# schematic1.net
KiCad netlist of a schematic drawn in Altium Designer
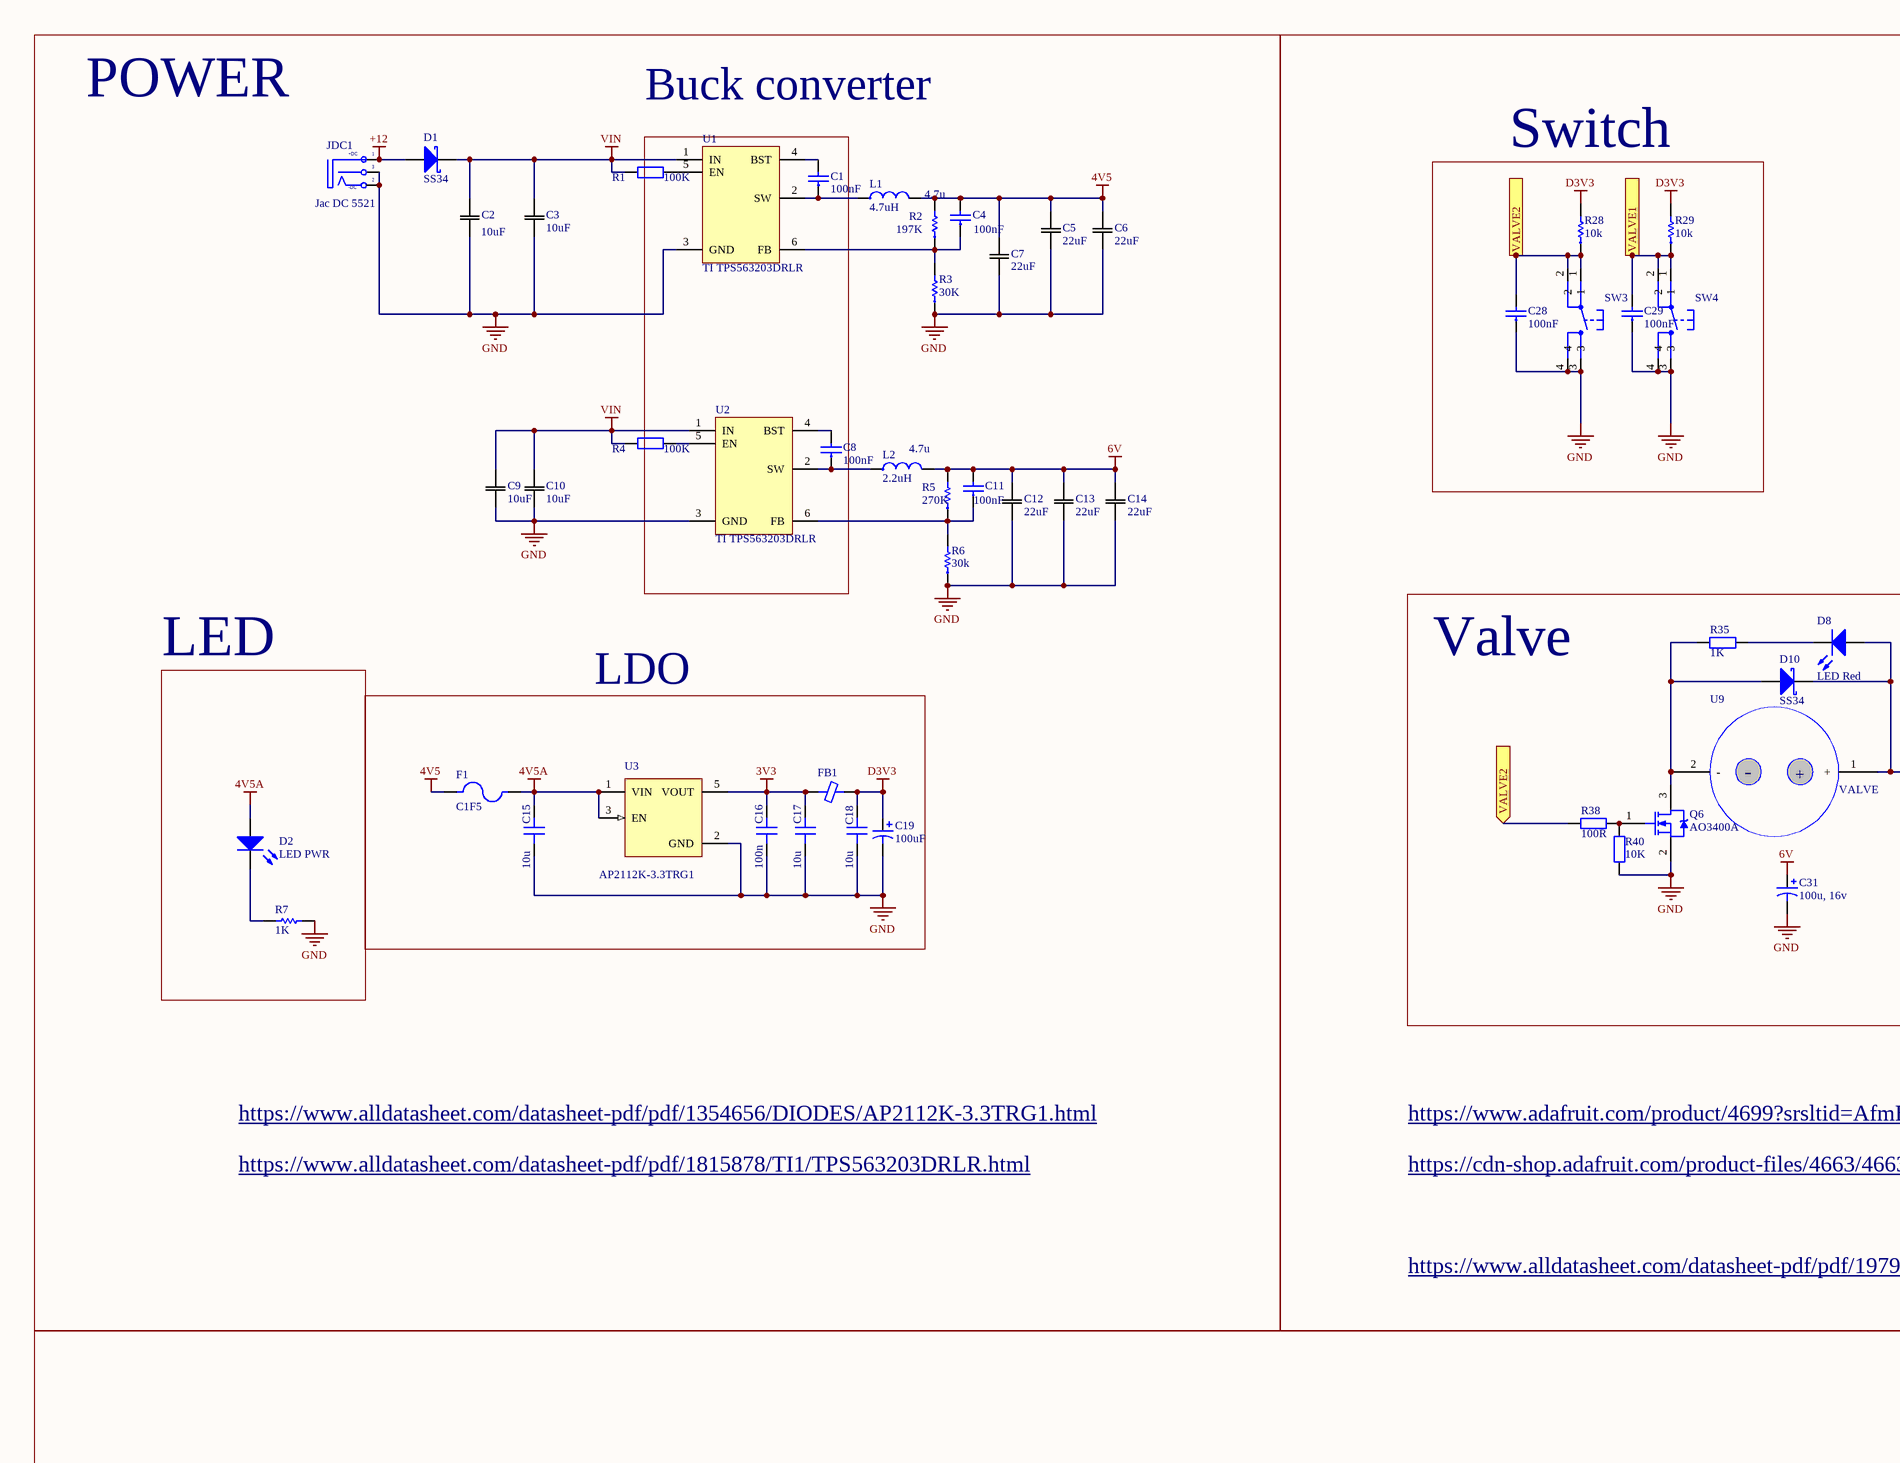
[diagram p0: schematic1.SchDoc, top left]
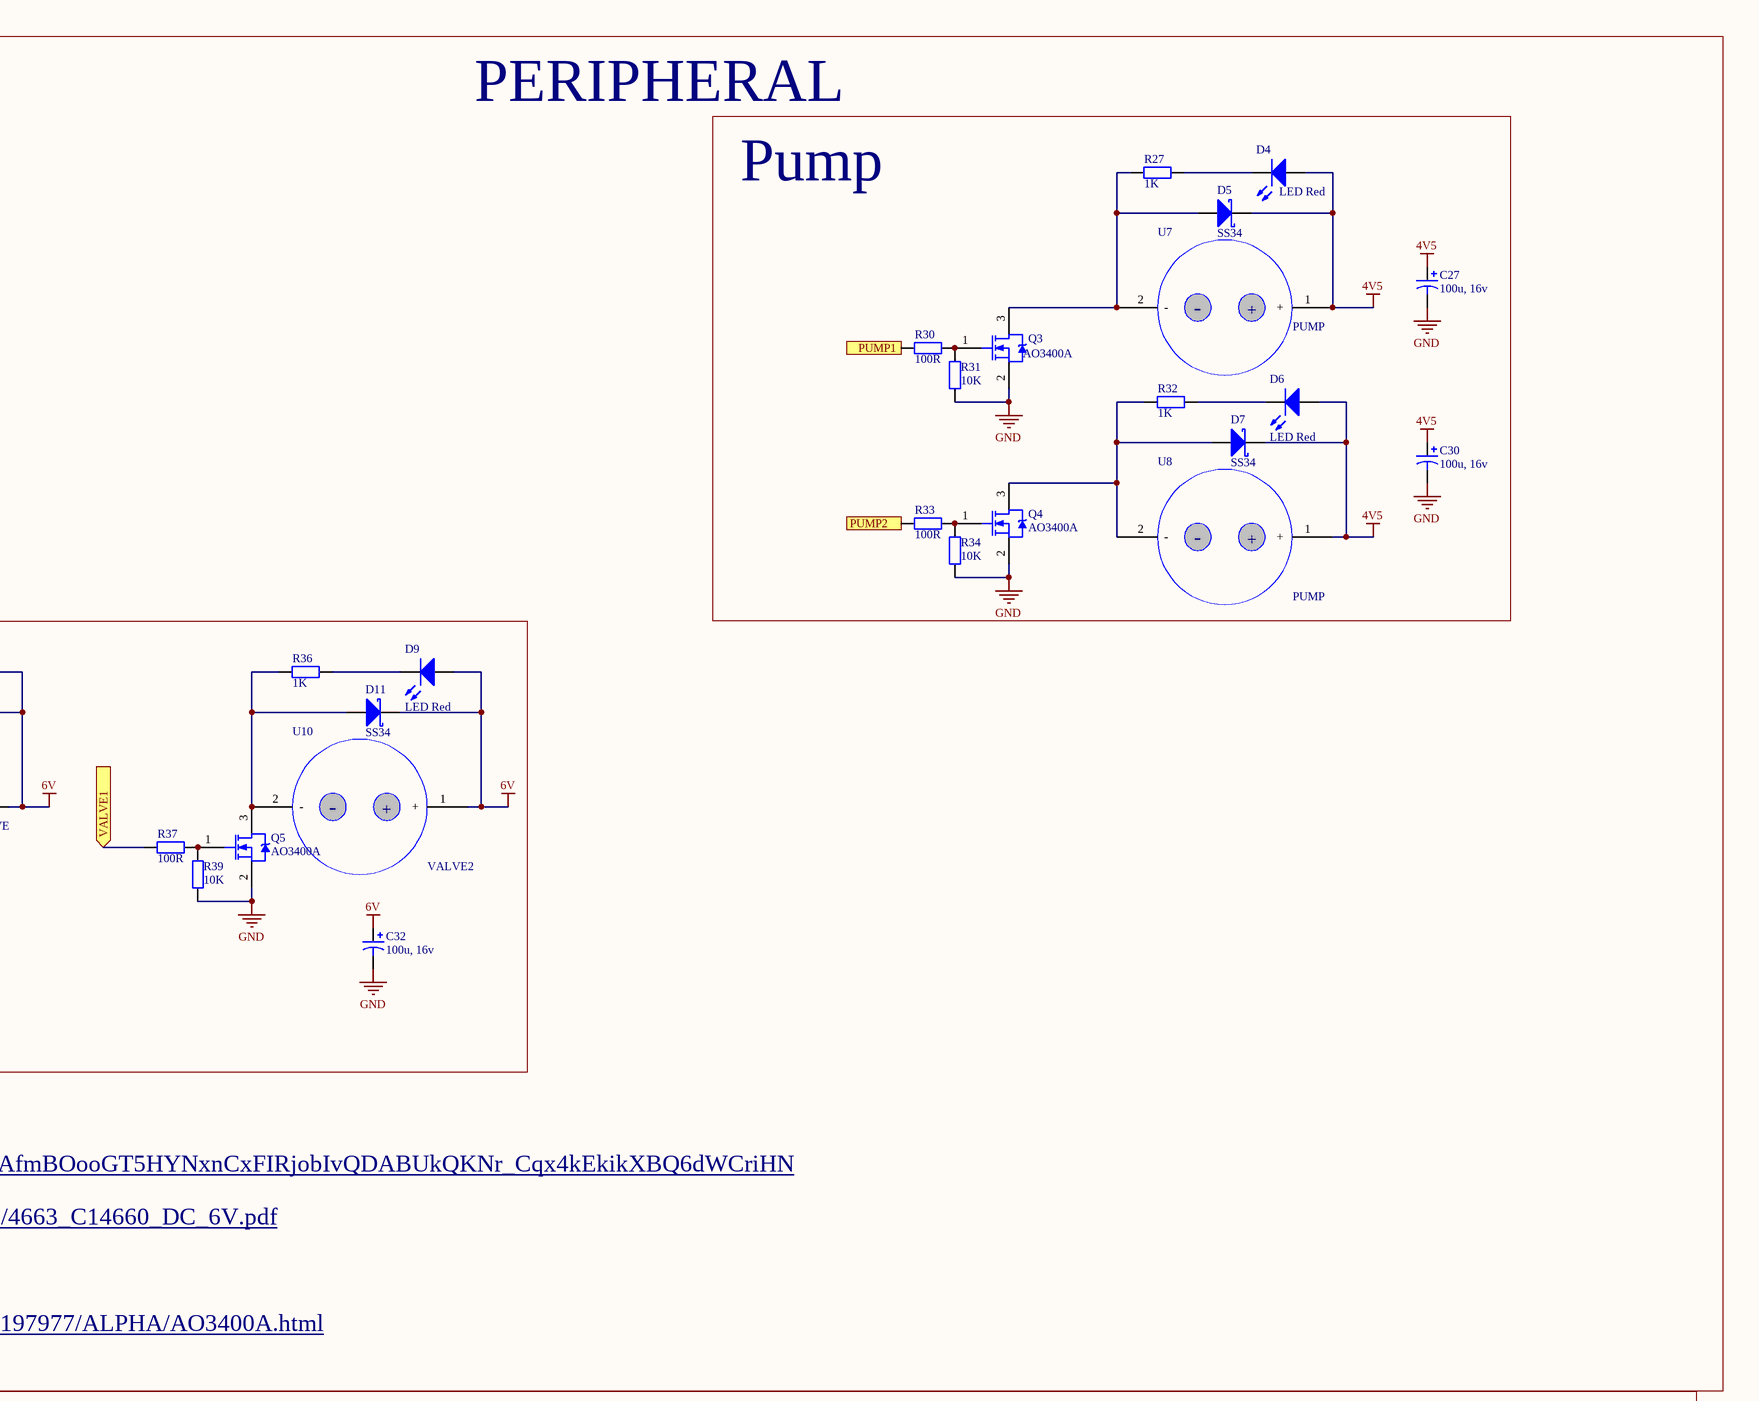
[diagram p1: schematic1.SchDoc, top right]
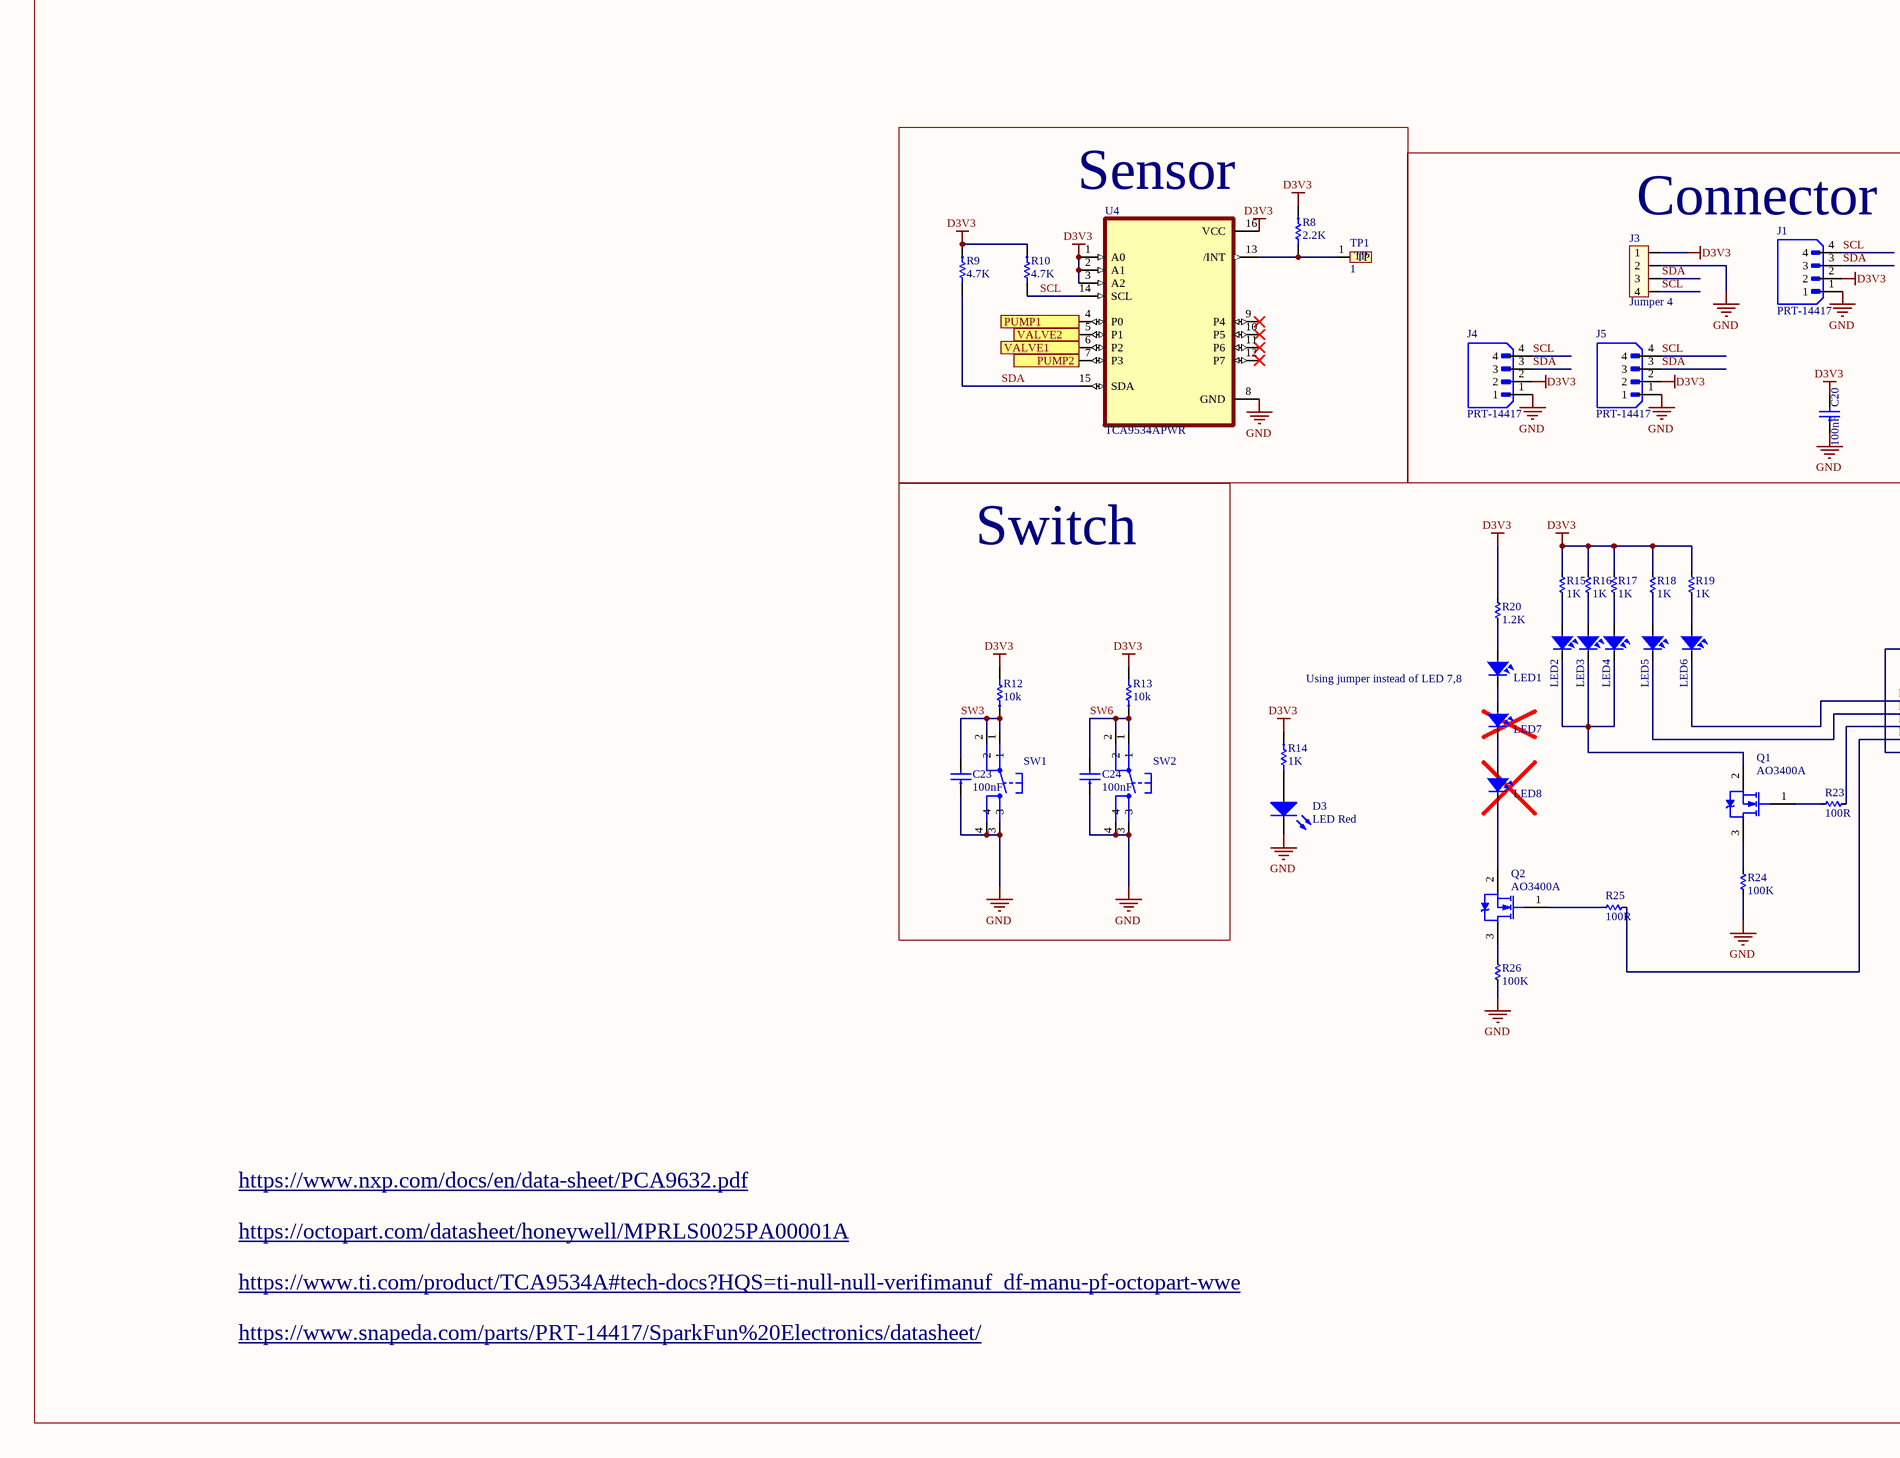
[diagram p2: schematic1.SchDoc, bottom left]
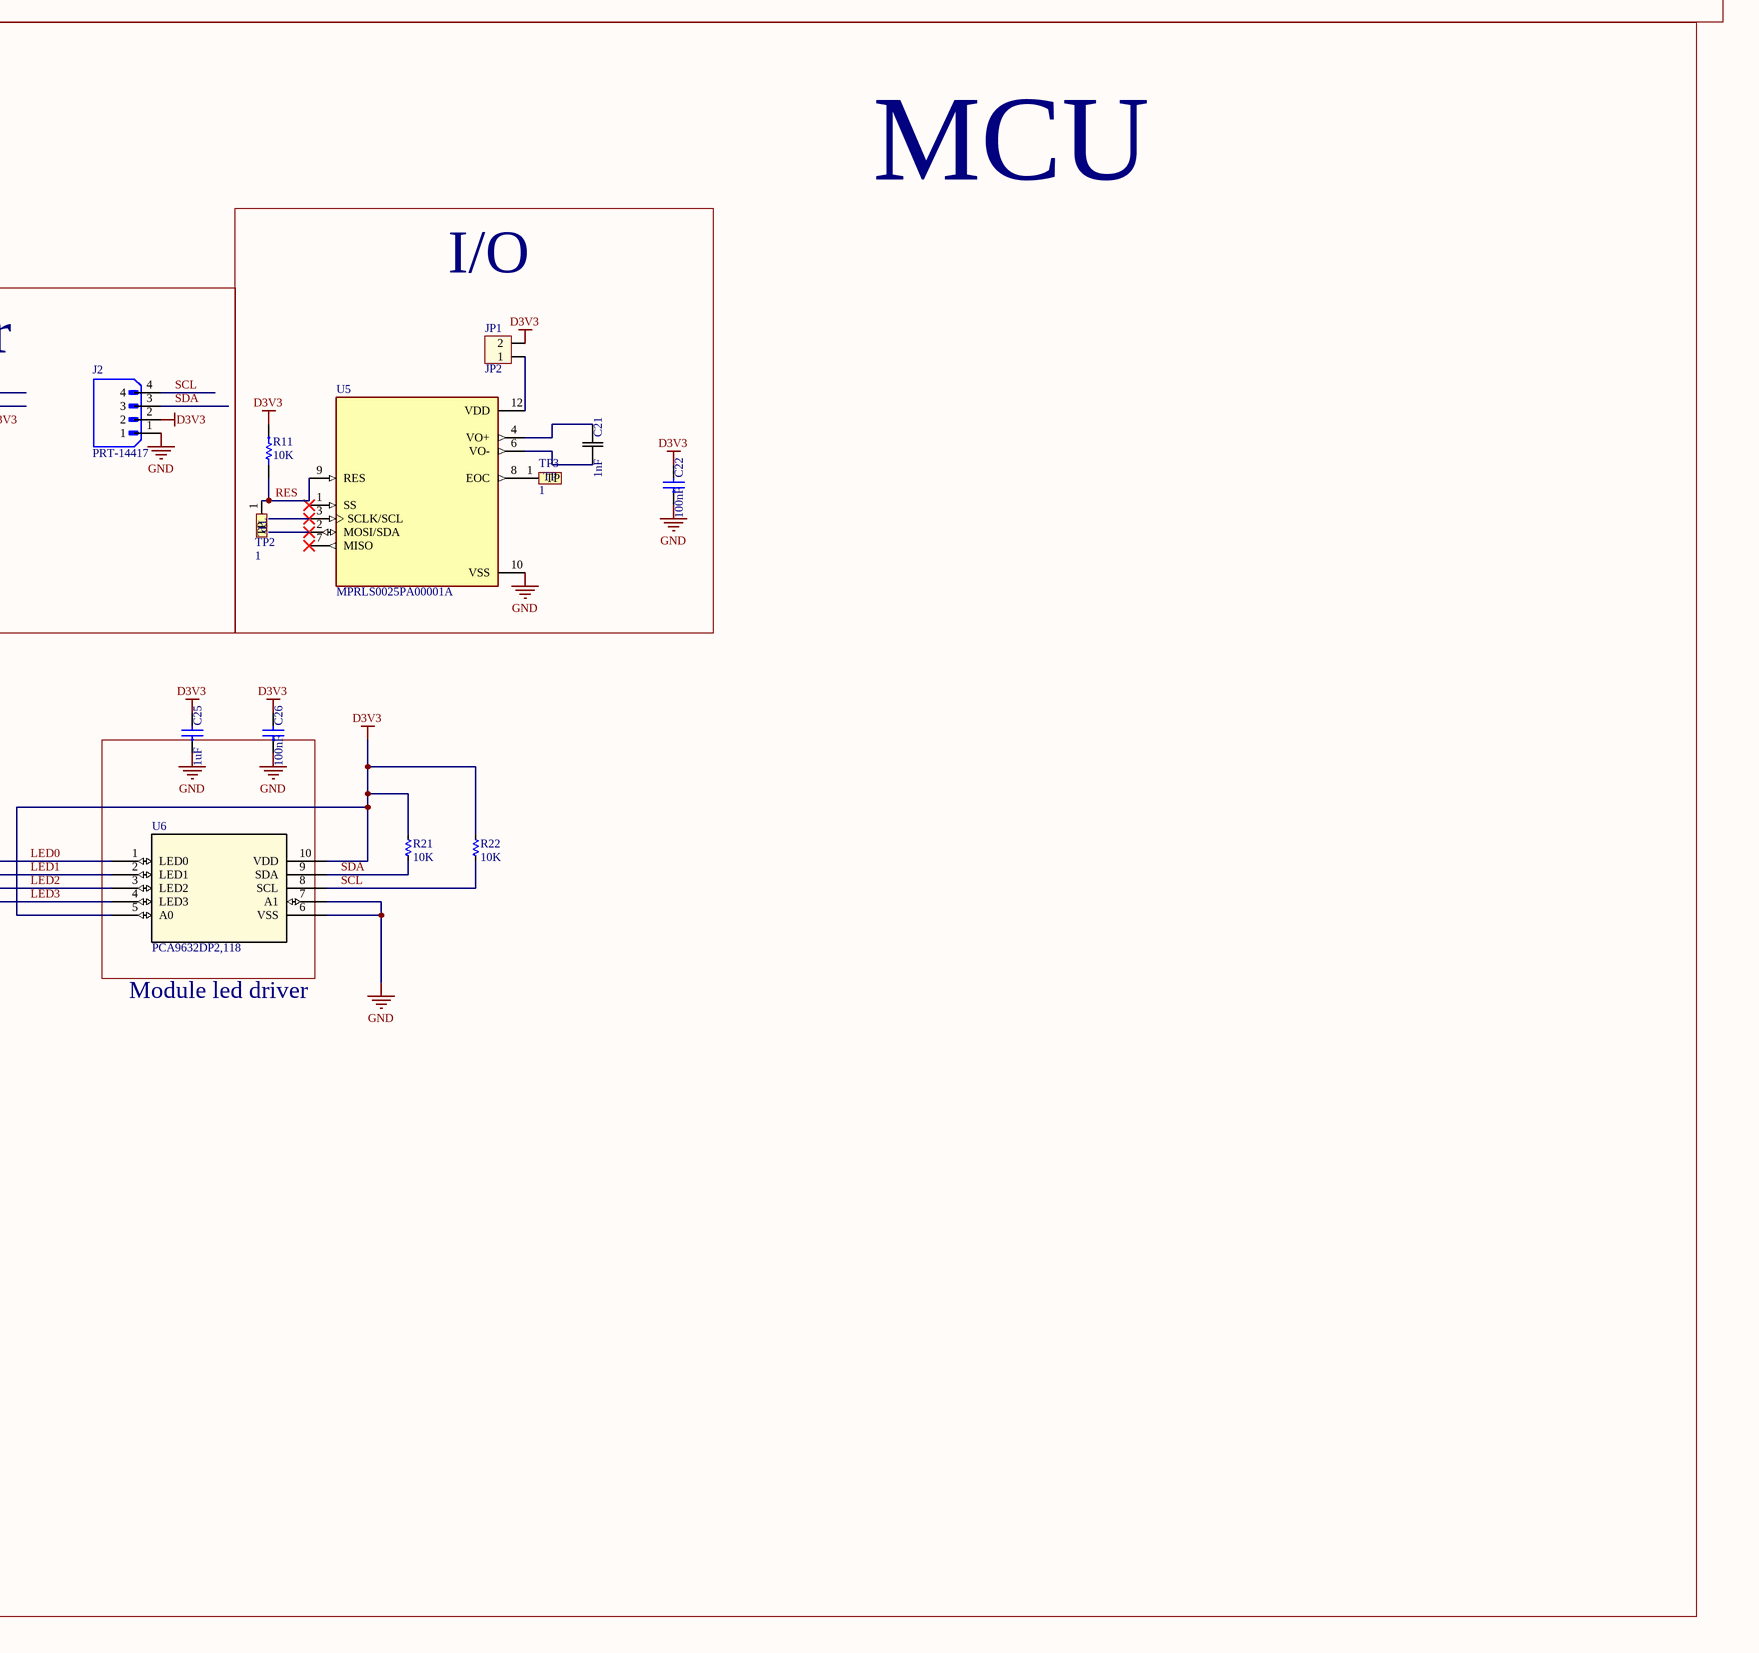
[diagram p3: schematic1.SchDoc, bottom right]

(export (version "E")
  (design (tool "Eeschema 10.0.6"))
  (components
    (comp (ref "C1")
      (value "100nF")
      (footprint "CN-SMD-0603")
      (description "CAP CER 100nF 10% 50V X7R 0603 SMD")
      (libsource (lib "2502-GMQLITE-MAIN") (part "CAPCER0001 100nF 10% 50V X7R 0603 SMD_1"))
    )
    (comp (ref "C2")
      (value "10uF")
      (footprint "CL10A106MQ8NNNC:CAP_CL10_SAM")
      (description "Description")
      (fields
        (field (name "MANUFACTURER_PART_NUMBER") "CL10A106MQ8NNNC")
        (field (name "COPYRIGHT") "Copyright (C) 2026 Ultra Librarian. All rights reserved.")
      )
      (libsource (lib "CL10A106MQ8NNNC") (part "CL10A106MQ8NNNC"))
    )
    (comp (ref "C3")
      (value "10uF")
      (footprint "CL10A106MQ8NNNC:CAP_CL10_SAM")
      (description "Description")
      (fields
        (field (name "MANUFACTURER_PART_NUMBER") "CL10A106MQ8NNNC")
        (field (name "COPYRIGHT") "Copyright (C) 2026 Ultra Librarian. All rights reserved.")
      )
      (libsource (lib "CL10A106MQ8NNNC") (part "CL10A106MQ8NNNC"))
    )
    (comp (ref "C4")
      (value "100nF")
      (footprint "CN-SMD-0603")
      (description "CAP CER 100nF 10% 50V X7R 0603 SMD")
      (libsource (lib "2502-GMQLITE-MAIN") (part "CAPCER0001 100nF 10% 50V X7R 0603 SMD"))
    )
    (comp (ref "C5")
      (value "22uF")
      (footprint "CN-SMD-0603")
      (description "Description")
      (fields
        (field (name "MANUFACTURER_PART_NUMBER") "GRM188R60J226MEA0D")
        (field (name "COPYRIGHT") "Copyright (C) 2026 Ultra Librarian. All rights reserved.")
      )
      (libsource (lib "GRM188R60J226MEA0D") (part "GRM188R60J226MEA0D"))
    )
    (comp (ref "C6")
      (value "22uF")
      (footprint "CN-SMD-0603")
      (description "Description")
      (fields
        (field (name "MANUFACTURER_PART_NUMBER") "GRM188R60J226MEA0D")
        (field (name "COPYRIGHT") "Copyright (C) 2026 Ultra Librarian. All rights reserved.")
      )
      (libsource (lib "GRM188R60J226MEA0D") (part "GRM188R60J226MEA0D"))
    )
    (comp (ref "C7")
      (value "22uF")
      (footprint "CN-SMD-0603")
      (description "Description")
      (fields
        (field (name "MANUFACTURER_PART_NUMBER") "GRM188R60J226MEA0D")
        (field (name "COPYRIGHT") "Copyright (C) 2026 Ultra Librarian. All rights reserved.")
      )
      (libsource (lib "GRM188R60J226MEA0D") (part "GRM188R60J226MEA0D"))
    )
    (comp (ref "C8")
      (value "100nF")
      (footprint "CN-SMD-0603")
      (description "CAP CER 100nF 10% 50V X7R 0603 SMD")
      (libsource (lib "2502-GMQLITE-MAIN") (part "CAPCER0001 100nF 10% 50V X7R 0603 SMD_1"))
    )
    (comp (ref "C9")
      (value "10uF")
      (footprint "CL10A106MQ8NNNC:CAP_CL10_SAM")
      (description "Description")
      (fields
        (field (name "MANUFACTURER_PART_NUMBER") "CL10A106MQ8NNNC")
        (field (name "COPYRIGHT") "Copyright (C) 2026 Ultra Librarian. All rights reserved.")
      )
      (libsource (lib "CL10A106MQ8NNNC") (part "CL10A106MQ8NNNC"))
    )
    (comp (ref "C10")
      (value "10uF")
      (footprint "CL10A106MQ8NNNC:CAP_CL10_SAM")
      (description "Description")
      (fields
        (field (name "MANUFACTURER_PART_NUMBER") "CL10A106MQ8NNNC")
        (field (name "COPYRIGHT") "Copyright (C) 2026 Ultra Librarian. All rights reserved.")
      )
      (libsource (lib "CL10A106MQ8NNNC") (part "CL10A106MQ8NNNC"))
    )
    (comp (ref "C11")
      (value "100nF")
      (footprint "CN-SMD-0603")
      (description "CAP CER 100nF 10% 50V X7R 0603 SMD")
      (libsource (lib "2502-GMQLITE-MAIN") (part "CAPCER0001 100nF 10% 50V X7R 0603 SMD"))
    )
    (comp (ref "C12")
      (value "22uF")
      (footprint "CN-SMD-0603")
      (description "Description")
      (fields
        (field (name "MANUFACTURER_PART_NUMBER") "GRM188R60J226MEA0D")
        (field (name "COPYRIGHT") "Copyright (C) 2026 Ultra Librarian. All rights reserved.")
      )
      (libsource (lib "GRM188R60J226MEA0D") (part "GRM188R60J226MEA0D"))
    )
    (comp (ref "C13")
      (value "22uF")
      (footprint "CN-SMD-0603")
      (description "Description")
      (fields
        (field (name "MANUFACTURER_PART_NUMBER") "GRM188R60J226MEA0D")
        (field (name "COPYRIGHT") "Copyright (C) 2026 Ultra Librarian. All rights reserved.")
      )
      (libsource (lib "GRM188R60J226MEA0D") (part "GRM188R60J226MEA0D"))
    )
    (comp (ref "C14")
      (value "22uF")
      (footprint "CN-SMD-0603")
      (description "Description")
      (fields
        (field (name "MANUFACTURER_PART_NUMBER") "GRM188R60J226MEA0D")
        (field (name "COPYRIGHT") "Copyright (C) 2026 Ultra Librarian. All rights reserved.")
      )
      (libsource (lib "GRM188R60J226MEA0D") (part "GRM188R60J226MEA0D"))
    )
    (comp (ref "C15")
      (value "10u")
      (footprint "CN-SMD-0603")
      (description "CAP0603 X7R 10UF 10% 10V")
      (fields
        (field (name "PART NUMBER") "GMC10X7R106K10NT")
        (field (name "MANUFACTURER") "Cal-Chip Electronics, Inc.")
      )
      (libsource (lib "Celestial Altium Library - altium_library") (part "Capacitor"))
    )
    (comp (ref "C16")
      (value "100n")
      (footprint "CN-SMD-0603")
      (description "CAP0603 X7R 100nF 10% 10V")
      (fields
        (field (name "PART NUMBER") "GMC10X7R106K10NT")
        (field (name "MANUFACTURER") "Cal-Chip Electronics, Inc.")
      )
      (libsource (lib "Celestial Altium Library - altium_library") (part "Capacitor"))
    )
    (comp (ref "C17")
      (value "10u")
      (footprint "CN-SMD-0603")
      (description "CAP0603 X7R 10UF 10% 10V")
      (fields
        (field (name "PART NUMBER") "GMC10X7R106K10NT")
        (field (name "MANUFACTURER") "Cal-Chip Electronics, Inc.")
      )
      (libsource (lib "Celestial Altium Library - altium_library") (part "Capacitor"))
    )
    (comp (ref "C18")
      (value "10u")
      (footprint "CN-SMD-0603")
      (description "CAP0603 X7R 10UF 10% 10V")
      (fields
        (field (name "PART NUMBER") "GMC10X7R106K10NT")
        (field (name "MANUFACTURER") "Cal-Chip Electronics, Inc.")
      )
      (libsource (lib "Celestial Altium Library - altium_library") (part "Capacitor"))
    )
    (comp (ref "C19")
      (value "100uF")
      (footprint "CAP-ALU-SMD-5.5x5.5")
      (description "CAP ALUM 100UF 20% \r\n16V SMD")
      (fields (field (name "Comment") "CAP ALUM 100UF 20% 16V SMD"))
      (libsource (lib "capacitor") (part "UWT1C101MCL1GB"))
    )
    (comp (ref "C20")
      (value "100nF")
      (footprint "CN-SMD-0603")
      (description "CAP CER 100nF 10% 50V X7R 0603 SMD")
      (libsource (lib "2502-GMQLITE-MAIN") (part "CAPCER0001 100nF 10% 50V X7R 0603 SMD"))
    )
    (comp (ref "C21")
      (value "1nF")
      (footprint "CN-SMD-0603")
      (description "No Description Available")
      (fields
        (field (name "MANUFACTURER_PART_NUMBER") "GCJ188R71H102KA01D")
        (field (name "COPYRIGHT") "Copyright (C) 2026 Ultra Librarian. All rights reserved.")
      )
      (libsource (lib "GCJ188R71H102KA01D") (part "GCJ188R71H102KA01D"))
    )
    (comp (ref "C22")
      (value "100nF")
      (footprint "CL10A106MQ8NNNC:CAP_CL10_SAM-L")
      (description "CAP CER 100nF 10% 50V X7R 0603 SMD")
      (libsource (lib "2502-GMQLITE-MAIN") (part "CAPCER0001 100nF 10% 50V X7R 0603 SMD"))
    )
    (comp (ref "C23")
      (value "100nF")
      (footprint "CN-SMD-0603")
      (description "CAP CER 100nF 10% 50V X7R 0603 SMD")
      (libsource (lib "2502-GMQLITE-MAIN") (part "CAPCER0001 100nF 10% 50V X7R 0603 SMD"))
    )
    (comp (ref "C24")
      (value "100nF")
      (footprint "CN-SMD-0603")
      (description "CAP CER 100nF 10% 50V X7R 0603 SMD")
      (libsource (lib "2502-GMQLITE-MAIN") (part "CAPCER0001 100nF 10% 50V X7R 0603 SMD"))
    )
    (comp (ref "C25")
      (value "1uF")
      (footprint "CL10A106MQ8NNNC:CAP_CL10_SAM-L")
      (description "CAP CER 100nF 10% 50V X7R 0603 SMD")
      (libsource (lib "2502-GMQLITE-MAIN") (part "CAPCER0001 100nF 10% 50V X7R 0603 SMD"))
    )
    (comp (ref "C26")
      (value "100nF")
      (footprint "CL10A106MQ8NNNC:CAP_CL10_SAM-L")
      (description "CAP CER 100nF 10% 50V X7R 0603 SMD")
      (libsource (lib "2502-GMQLITE-MAIN") (part "CAPCER0001 100nF 10% 50V X7R 0603 SMD"))
    )
    (comp (ref "C27")
      (value "100u, 16v")
      (footprint "CAP-ALU-SMD-5.5x5.5")
      (description "CAP ALUM 100UF 20% 16V SMD")
      (libsource (lib "capacitor") (part "UWT1C101MCL1GB"))
    )
    (comp (ref "C28")
      (value "100nF")
      (footprint "CN-SMD-0603")
      (description "CAP CER 100nF 10% 50V X7R 0603 SMD")
      (libsource (lib "2502-GMQLITE-MAIN") (part "CAPCER0001 100nF 10% 50V X7R 0603 SMD"))
    )
    (comp (ref "C29")
      (value "100nF")
      (footprint "CN-SMD-0603")
      (description "CAP CER 100nF 10% 50V X7R 0603 SMD")
      (libsource (lib "2502-GMQLITE-MAIN") (part "CAPCER0001 100nF 10% 50V X7R 0603 SMD"))
    )
    (comp (ref "C30")
      (value "100u, 16v")
      (footprint "CAP-ALU-SMD-5.5x5.5")
      (description "CAP ALUM 100UF 20% 16V SMD")
      (libsource (lib "capacitor") (part "UWT1C101MCL1GB"))
    )
    (comp (ref "C31")
      (value "100u, 16v")
      (footprint "CAP-ALU-SMD-5.5x5.5")
      (description "CAP ALUM 100UF 20% 16V SMD")
      (libsource (lib "capacitor") (part "UWT1C101MCL1GB"))
    )
    (comp (ref "C32")
      (value "100u, 16v")
      (footprint "CAP-ALU-SMD-5.5x5.5")
      (description "CAP ALUM 100UF 20% 16V SMD")
      (libsource (lib "capacitor") (part "UWT1C101MCL1GB"))
    )
    (comp (ref "D1")
      (value "SS34")
      (footprint "DIO-SMD-106")
      (description "Schottky Diode 40V 3A SMA")
      (libsource (lib "diode") (part "SS34"))
    )
    (comp (ref "D2")
      (value "LED PWR")
      (footprint "LED-0805-Red")
      (description "Lite-On LED Red 0603")
      (fields (field (name "Comment") "LED Red"))
      (libsource (lib "diode") (part "LTST-C190KRKT"))
    )
    (comp (ref "D3")
      (value "LED Red")
      (footprint "LED-0805-Red")
      (description "Lite-On LED Red 0603")
      (libsource (lib "diode") (part "LTST-C190KRKT"))
    )
    (comp (ref "D4")
      (value "LED Red")
      (footprint "LED-0805-Red")
      (description "Lite-On LED Red 0603")
      (libsource (lib "diode") (part "LTST-C190KRKT"))
    )
    (comp (ref "D5")
      (value "SS34")
      (footprint "DIO-SMD-106")
      (description "Schottky Diode 40V 3A SMA")
      (libsource (lib "diode") (part "SS34"))
    )
    (comp (ref "D6")
      (value "LED Red")
      (footprint "LED-0805-Red")
      (description "Lite-On LED Red 0603")
      (libsource (lib "diode") (part "LTST-C190KRKT"))
    )
    (comp (ref "D7")
      (value "SS34")
      (footprint "DIO-SMD-106")
      (description "Schottky Diode 40V 3A SMA")
      (libsource (lib "diode") (part "SS34"))
    )
    (comp (ref "D8")
      (value "LED Red")
      (footprint "LED-0805-Red")
      (description "Lite-On LED Red 0603")
      (libsource (lib "diode") (part "LTST-C190KRKT"))
    )
    (comp (ref "D9")
      (value "LED Red")
      (footprint "LED-0805-Red")
      (description "Lite-On LED Red 0603")
      (libsource (lib "diode") (part "LTST-C190KRKT"))
    )
    (comp (ref "D10")
      (value "SS34")
      (footprint "DIO-SMD-106")
      (description "Schottky Diode 40V 3A SMA")
      (libsource (lib "diode") (part "SS34"))
    )
    (comp (ref "D11")
      (value "SS34")
      (footprint "DIO-SMD-106")
      (description "Schottky Diode 40V 3A SMA")
      (libsource (lib "diode") (part "SS34"))
    )
    (comp (ref "F1")
      (value "C1F5")
      (footprint "RES-SMD-1206")
      (description "Fuse Chip Fast Acting 5A 125V SMD Solder Pad 1206 3.2 X 1.58 X 0.63mm")
      (fields (field (name "MANUFACTURER") "Bel TRP"))
      (libsource (lib "POWER_PIN_CAMERA") (part "C1F5"))
    )
    (comp (ref "FB1")
      (value "330")
      (footprint "IND_BLM18KG331WH1D_MUR-L")
      (description "FERRITE BEAD 330 OHM 0603 1LN")
      (fields
        (field (name "PART NUMBER") "BLM18KG331SH1D")
        (field (name "MANUFACTURER") "Murata Electronics")
      )
      (libsource (lib "Celestial Altium Library - altium_library") (part "Ferrite Chip"))
    )
    (comp (ref "J1")
      (value "PRT-14417")
      (footprint "SPARKFUN_PRT-14417")
      (description "QWIIC JST CONNECTOR - SMD 4-PIN")
      (fields (field (name "MF") "SparkFun Electronics"))
      (libsource (lib "PRT-14417") (part "PRT-14417"))
    )
    (comp (ref "J2")
      (value "PRT-14417")
      (footprint "SPARKFUN_PRT-14417")
      (description "QWIIC JST CONNECTOR - SMD 4-PIN")
      (fields (field (name "MF") "SparkFun Electronics"))
      (libsource (lib "PRT-14417") (part "PRT-14417"))
    )
    (comp (ref "J3")
      (value "Jumper 4")
      (footprint "JP4")
      (description "Jumper 3")
      (libsource (lib "hanguyen") (part "JP4"))
    )
    (comp (ref "J4")
      (value "PRT-14417")
      (footprint "SPARKFUN_PRT-14417")
      (description "QWIIC JST CONNECTOR - SMD 4-PIN")
      (fields (field (name "MF") "SparkFun Electronics"))
      (libsource (lib "PRT-14417") (part "PRT-14417"))
    )
    (comp (ref "J5")
      (value "PRT-14417")
      (footprint "SPARKFUN_PRT-14417")
      (description "QWIIC JST CONNECTOR - SMD 4-PIN")
      (fields (field (name "MF") "SparkFun Electronics"))
      (libsource (lib "PRT-14417") (part "PRT-14417"))
    )
    (comp (ref "JDC1")
      (value "Jac DC 5521")
      (footprint "DC0")
      (description "Jac DC input")
      (libsource (lib "2502-GMQLITE-MAIN") (part "DCIN"))
    )
    (comp (ref "JP1")
      (value "JP2")
      (footprint "JP2-CLOSED")
      (description "jumper 2.0 B")
      (libsource (lib "hanguyen") (part "Con2"))
    )
    (comp (ref "L1")
      (value "4.7uH")
      (footprint "Inductor_SMD")
      (description "IND MOI 1W2T 4.7uH 20% 5A 0420 SMD")
      (fields (field (name "ALTIUM_VALUE") "4.7u"))
      (libsource (lib "2502-GMQLITE-MAIN") (part "INDMOI0016 1W2T 2.2uH 20% 5A 0420 SMD"))
    )
    (comp (ref "L2")
      (value "2.2uH")
      (footprint "Inductor_SMD")
      (description "IND MOI 1W2T 4.7uH 20% 5A 0420 SMD")
      (fields (field (name "ALTIUM_VALUE") "4.7u"))
      (libsource (lib "2502-GMQLITE-MAIN") (part "INDMOI0016 1W2T 2.2uH 20% 5A 0420 SMD"))
    )
    (comp (ref "LED1")
      (value "LED")
      (footprint "LED-1206-Red")
      (description "LED Single colour Green and Red")
      (libsource (lib "Copy of KhanhBK_SCH_Library_1") (part "LED"))
    )
    (comp (ref "LED2")
      (value "LED")
      (footprint "LED-1206-Red")
      (description "LED Single colour Green and Red")
      (libsource (lib "Copy of KhanhBK_SCH_Library_1") (part "LED"))
    )
    (comp (ref "LED3")
      (value "LED")
      (footprint "LED-1206-Red")
      (description "LED Single colour Green and Red")
      (libsource (lib "Copy of KhanhBK_SCH_Library_1") (part "LED"))
    )
    (comp (ref "LED4")
      (value "LED")
      (footprint "LED-1206-Red")
      (description "LED Single colour Green and Red")
      (libsource (lib "Copy of KhanhBK_SCH_Library_1") (part "LED"))
    )
    (comp (ref "LED5")
      (value "LED")
      (footprint "LED-1206-Red")
      (description "LED Single colour Green and Red")
      (libsource (lib "Copy of KhanhBK_SCH_Library_1") (part "LED"))
    )
    (comp (ref "LED6")
      (value "LED")
      (footprint "LED-1206-Red")
      (description "LED Single colour Green and Red")
      (libsource (lib "Copy of KhanhBK_SCH_Library_1") (part "LED"))
    )
    (comp (ref "LED7")
      (value "LED")
      (footprint "LED-1206-Red")
      (description "LED Single colour Green and Red")
      (libsource (lib "Copy of KhanhBK_SCH_Library_1") (part "LED"))
    )
    (comp (ref "LED8")
      (value "LED")
      (footprint "LED-1206-Red")
      (description "LED Single colour Green and Red")
      (libsource (lib "Copy of KhanhBK_SCH_Library_1") (part "LED"))
    )
    (comp (ref "Q1")
      (value "AO3400A")
      (footprint "SOT-23-3L_AOS-L")
      (description "MOSFET N-CH 25V 5.8A SOT23")
      (libsource (lib "fet") (part "IRFML8244TRPBF"))
    )
    (comp (ref "Q2")
      (value "AO3400A")
      (footprint "SOT-23-3L_AOS-L")
      (description "MOSFET N-CH 25V 5.8A SOT23")
      (libsource (lib "fet") (part "IRFML8244TRPBF"))
    )
    (comp (ref "Q3")
      (value "AO3400A")
      (footprint "SOT-23-3L_AOS")
      (description "MOSFET N-CH 25V 5.8A SOT23")
      (libsource (lib "fet") (part "IRFML8244TRPBF"))
    )
    (comp (ref "Q4")
      (value "AO3400A")
      (footprint "SOT-23-3L_AOS-L")
      (description "MOSFET N-CH 25V 5.8A SOT23")
      (libsource (lib "fet") (part "IRFML8244TRPBF"))
    )
    (comp (ref "Q5")
      (value "AO3400A")
      (footprint "SOT-23-3L_AOS-L")
      (description "MOSFET N-CH 25V 5.8A SOT23")
      (libsource (lib "fet") (part "IRFML8244TRPBF"))
    )
    (comp (ref "Q6")
      (value "AO3400A")
      (footprint "SOT-23-3L_AOS-L")
      (description "MOSFET N-CH 25V 5.8A SOT23")
      (libsource (lib "fet") (part "IRFML8244TRPBF"))
    )
    (comp (ref "R1")
      (value "100K")
      (footprint "RES-SMD-0603")
      (description "Yageo RES 100K 5% 1/10W 0603")
      (fields (field (name "Comment") "RES 100K 5% 1/10W 0603"))
      (libsource (lib "resistor") (part "RC0603JR-07100KL"))
    )
    (comp (ref "R2")
      (value "197K")
      (footprint "RES-SMD-0603")
      (description "RES CHP 2K7 1% 1/10W 0603 SMD")
      (libsource (lib "2502-GMQLITE-MAIN") (part "RESCHP0195 2K7 1% 0603 SMD"))
    )
    (comp (ref "R3")
      (value "30K")
      (footprint "RES-SMD-0603")
      (description "RES CHP 2K7 1% 1/10W 0603 SMD")
      (libsource (lib "2502-GMQLITE-MAIN") (part "RESCHP0195 2K7 1% 0603 SMD"))
    )
    (comp (ref "R4")
      (value "100K")
      (footprint "RES-SMD-0603")
      (description "Yageo RES 100K 5% 1/10W 0603")
      (fields (field (name "Comment") "RES 100K 5% 1/10W 0603"))
      (libsource (lib "resistor") (part "RC0603JR-07100KL"))
    )
    (comp (ref "R5")
      (value "270K")
      (footprint "RES-SMD-0603")
      (description "RES CHP 2K7 1% 1/10W 0603 SMD")
      (libsource (lib "2502-GMQLITE-MAIN") (part "RESCHP0195 2K7 1% 0603 SMD"))
    )
    (comp (ref "R6")
      (value "30k")
      (footprint "RES-SMD-0603")
      (description "RES CHP 2K7 1% 1/10W 0603 SMD")
      (libsource (lib "2502-GMQLITE-MAIN") (part "RESCHP0195 2K7 1% 0603 SMD"))
    )
    (comp (ref "R7")
      (value "1K")
      (footprint "RES-SMD-0603")
      (description "Res Thick Film 0603 2.2K Ohm 5% 1/10W ±200ppm/°C Molded SMD SMD Paper T/R")
      (fields
        (field (name "MANUFACTURER") "Vishay")
        (field (name "MANUFACTURER PART NUMBER") "CRCW06032K20JNEA")
      )
      (libsource (lib "Stm32_Flyback_Driver_250814_1") (part "Resistor 2.2K"))
    )
    (comp (ref "R8")
      (value "2.2K")
      (footprint "RES-SMD-0603")
      (description "RES CHP 8K4 1% 1/10W 0603 SMD")
      (libsource (lib "2502-GMQLITE-MAIN") (part "RESCHP0428 8K4 1% 0603 SMD"))
    )
    (comp (ref "R9")
      (value "4.7K")
      (footprint "RES-SMD-0603")
      (description "RES CHP 8K4 1% 1/10W 0603 SMD")
      (libsource (lib "2502-GMQLITE-MAIN") (part "RESCHP0428 8K4 1% 0603 SMD"))
    )
    (comp (ref "R10")
      (value "4.7K")
      (footprint "RES-SMD-0603")
      (description "RES CHP 8K4 1% 1/10W 0603 SMD")
      (libsource (lib "2502-GMQLITE-MAIN") (part "RESCHP0428 8K4 1% 0603 SMD"))
    )
    (comp (ref "R11")
      (value "10K")
      (footprint "RES-SMD-0603")
      (description "RES CHP 8K4 1% 1/10W 0603 SMD")
      (libsource (lib "2502-GMQLITE-MAIN") (part "RESCHP0428 8K4 1% 0603 SMD"))
    )
    (comp (ref "R12")
      (value "10k")
      (footprint "RES-SMD-0603")
      (description "RES CHP 8K4 1% 1/10W 0603 SMD")
      (libsource (lib "2502-GMQLITE-MAIN") (part "RESCHP0428 8K4 1% 0603 SMD"))
    )
    (comp (ref "R13")
      (value "10k")
      (footprint "RES-SMD-0603")
      (description "RES CHP 8K4 1% 1/10W 0603 SMD")
      (libsource (lib "2502-GMQLITE-MAIN") (part "RESCHP0428 8K4 1% 0603 SMD"))
    )
    (comp (ref "R14")
      (value "1K")
      (footprint "RES-SMD-0603")
      (description "RES CHP 8K4 1% 1/10W 0603 SMD")
      (libsource (lib "2502-GMQLITE-MAIN") (part "RESCHP0428 8K4 1% 0603 SMD"))
    )
    (comp (ref "R15")
      (value "1K")
      (footprint "RES-SMD-0603")
      (description "Resistor")
      (fields
        (field (name "MANUFACTURER") "Generic Components")
        (field (name "PUBLISHER") "Altium Hobart Technology Centre")
      )
      (libsource (lib "Copy of KhanhBK_SCH_Library_1") (part "Res-SMD"))
    )
    (comp (ref "R16")
      (value "1K")
      (footprint "RES-SMD-0603")
      (description "Resistor")
      (fields
        (field (name "MANUFACTURER") "Generic Components")
        (field (name "PUBLISHER") "Altium Hobart Technology Centre")
      )
      (libsource (lib "Copy of KhanhBK_SCH_Library_1") (part "Res-SMD"))
    )
    (comp (ref "R17")
      (value "1K")
      (footprint "RES-SMD-0603")
      (description "Resistor")
      (fields
        (field (name "MANUFACTURER") "Generic Components")
        (field (name "PUBLISHER") "Altium Hobart Technology Centre")
      )
      (libsource (lib "Copy of KhanhBK_SCH_Library_1") (part "Res-SMD"))
    )
    (comp (ref "R18")
      (value "1K")
      (footprint "RES-SMD-0603")
      (description "Resistor")
      (fields
        (field (name "MANUFACTURER") "Generic Components")
        (field (name "PUBLISHER") "Altium Hobart Technology Centre")
      )
      (libsource (lib "Copy of KhanhBK_SCH_Library_1") (part "Res-SMD"))
    )
    (comp (ref "R19")
      (value "1K")
      (footprint "RES-SMD-0603")
      (description "Resistor")
      (fields
        (field (name "MANUFACTURER") "Generic Components")
        (field (name "PUBLISHER") "Altium Hobart Technology Centre")
      )
      (libsource (lib "Copy of KhanhBK_SCH_Library_1") (part "Res-SMD"))
    )
    (comp (ref "R20")
      (value "1.2K")
      (footprint "RES-SMD-0603")
      (description "Resistor")
      (fields
        (field (name "MANUFACTURER") "Generic Components")
        (field (name "PUBLISHER") "Altium Hobart Technology Centre")
      )
      (libsource (lib "Copy of KhanhBK_SCH_Library_1") (part "Res-SMD"))
    )
    (comp (ref "R21")
      (value "10K")
      (footprint "RES-SMD-0603")
      (description "Resistor")
      (fields
        (field (name "MANUFACTURER") "Generic Components")
        (field (name "PUBLISHER") "Altium Hobart Technology Centre")
      )
      (libsource (lib "Copy of KhanhBK_SCH_Library_1") (part "Res-SMD"))
    )
    (comp (ref "R22")
      (value "10K")
      (footprint "RES-SMD-0603")
      (description "Resistor")
      (fields
        (field (name "MANUFACTURER") "Generic Components")
        (field (name "PUBLISHER") "Altium Hobart Technology Centre")
      )
      (libsource (lib "Copy of KhanhBK_SCH_Library_1") (part "Res-SMD"))
    )
    (comp (ref "R23")
      (value "100R")
      (footprint "RES-SMD-0603")
      (description "Resistor")
      (fields
        (field (name "MANUFACTURER") "Generic Components")
        (field (name "PUBLISHER") "Altium Hobart Technology Centre")
      )
      (libsource (lib "Copy of KhanhBK_SCH_Library_1") (part "Res-SMD"))
    )
    (comp (ref "R24")
      (value "100K")
      (footprint "RES-SMD-0603")
      (description "Resistor")
      (fields
        (field (name "MANUFACTURER") "Generic Components")
        (field (name "PUBLISHER") "Altium Hobart Technology Centre")
      )
      (libsource (lib "Copy of KhanhBK_SCH_Library_1") (part "Res-SMD"))
    )
    (comp (ref "R25")
      (value "100R")
      (footprint "RES-SMD-0603")
      (description "Resistor")
      (fields
        (field (name "MANUFACTURER") "Generic Components")
        (field (name "PUBLISHER") "Altium Hobart Technology Centre")
      )
      (libsource (lib "Copy of KhanhBK_SCH_Library_1") (part "Res-SMD"))
    )
    (comp (ref "R26")
      (value "100K")
      (footprint "RES-SMD-0603")
      (description "Resistor")
      (fields
        (field (name "MANUFACTURER") "Generic Components")
        (field (name "PUBLISHER") "Altium Hobart Technology Centre")
      )
      (libsource (lib "Copy of KhanhBK_SCH_Library_1") (part "Res-SMD"))
    )
    (comp (ref "R27")
      (value "1K")
      (footprint "RES-SMD-0603")
      (description "Yageo RES 1K 5% 1/10W 0603")
      (fields (field (name "Comment") "RES 1K 5% 1/10W 0603"))
      (libsource (lib "resistor") (part "RC0603JR-071KL"))
    )
    (comp (ref "R28")
      (value "10k")
      (footprint "RES-SMD-0603")
      (description "RES CHP 8K4 1% 1/10W 0603 SMD")
      (libsource (lib "2502-GMQLITE-MAIN") (part "RESCHP0428 8K4 1% 0603 SMD"))
    )
    (comp (ref "R29")
      (value "10k")
      (footprint "RES-SMD-0603")
      (description "RES CHP 8K4 1% 1/10W 0603 SMD")
      (libsource (lib "2502-GMQLITE-MAIN") (part "RESCHP0428 8K4 1% 0603 SMD"))
    )
    (comp (ref "R30")
      (value "100R")
      (footprint "RES-SMD-0603")
      (description "Yageo RES 100R 5% 1/10W 0603")
      (fields (field (name "Comment") "RES 100R 5% 1/10W 0603"))
      (libsource (lib "resistor") (part "RC0603JR-07100RL"))
    )
    (comp (ref "R31")
      (value "10K")
      (footprint "RES-SMD-0603")
      (description "Yageo RES 10K 5% 1/10W 0603")
      (fields (field (name "Comment") "RES 10K 5% 1/10W 0603"))
      (libsource (lib "resistor") (part "RC0603JR-0710KL"))
    )
    (comp (ref "R32")
      (value "1K")
      (footprint "RES-SMD-0603")
      (description "Yageo RES 1K 5% 1/10W 0603")
      (fields (field (name "Comment") "RES 1K 5% 1/10W 0603"))
      (libsource (lib "resistor") (part "RC0603JR-071KL"))
    )
    (comp (ref "R33")
      (value "100R")
      (footprint "RES-SMD-0603")
      (description "Yageo RES 100R 5% 1/10W 0603")
      (fields (field (name "Comment") "RES 100R 5% 1/10W 0603"))
      (libsource (lib "resistor") (part "RC0603JR-07100RL"))
    )
    (comp (ref "R34")
      (value "10K")
      (footprint "RES-SMD-0603")
      (description "Yageo RES 10K 5% 1/10W 0603")
      (fields (field (name "Comment") "RES 10K 5% 1/10W 0603"))
      (libsource (lib "resistor") (part "RC0603JR-0710KL"))
    )
    (comp (ref "R35")
      (value "1K")
      (footprint "RES-SMD-0603")
      (description "Yageo RES 1K 5% 1/10W 0603")
      (fields (field (name "Comment") "RES 1K 5% 1/10W 0603"))
      (libsource (lib "resistor") (part "RC0603JR-071KL"))
    )
    (comp (ref "R36")
      (value "1K")
      (footprint "RES-SMD-0603")
      (description "Yageo RES 1K 5% 1/10W 0603")
      (fields (field (name "Comment") "RES 1K 5% 1/10W 0603"))
      (libsource (lib "resistor") (part "RC0603JR-071KL"))
    )
    (comp (ref "R37")
      (value "100R")
      (footprint "RES-SMD-0603")
      (description "Yageo RES 100R 5% 1/10W 0603")
      (fields (field (name "Comment") "RES 100R 5% 1/10W 0603"))
      (libsource (lib "resistor") (part "RC0603JR-07100RL"))
    )
    (comp (ref "R38")
      (value "100R")
      (footprint "RES-SMD-0603")
      (description "Yageo RES 100R 5% 1/10W 0603")
      (fields (field (name "Comment") "RES 100R 5% 1/10W 0603"))
      (libsource (lib "resistor") (part "RC0603JR-07100RL"))
    )
    (comp (ref "R39")
      (value "10K")
      (footprint "RES-SMD-0603")
      (description "Yageo RES 10K 5% 1/10W 0603")
      (fields (field (name "Comment") "RES 10K 5% 1/10W 0603"))
      (libsource (lib "resistor") (part "RC0603JR-0710KL"))
    )
    (comp (ref "R40")
      (value "10K")
      (footprint "RES-SMD-0603")
      (description "Yageo RES 10K 5% 1/10W 0603")
      (fields (field (name "Comment") "RES 10K 5% 1/10W 0603"))
      (libsource (lib "resistor") (part "RC0603JR-0710KL"))
    )
    (comp (ref "SW1")
      (value "SW2")
      (footprint "BUTTON 4 PIN")
      (description "Switch button 4 pin")
      (libsource (lib "Stm32_Flyback_Driver_250814_1") (part "SW2"))
    )
    (comp (ref "SW2")
      (value "SW2")
      (footprint "BUTTON 4 PIN")
      (description "Switch button 4 pin")
      (libsource (lib "Stm32_Flyback_Driver_250814_1") (part "SW2"))
    )
    (comp (ref "SW3")
      (value "SW2")
      (footprint "BUTTON 4 PIN")
      (description "Switch button 4 pin")
      (libsource (lib "Stm32_Flyback_Driver_250814_1") (part "SW2"))
    )
    (comp (ref "SW4")
      (value "SW2")
      (footprint "BUTTON 4 PIN")
      (description "Switch button 4 pin")
      (libsource (lib "Stm32_Flyback_Driver_250814_1") (part "SW2"))
    )
    (comp (ref "TP1")
      (value "1")
      (footprint "TP - 2")
      (description "CONNECT 1")
      (libsource (lib "") (part "TP_1"))
    )
    (comp (ref "TP2")
      (value "1")
      (footprint "TP - 2")
      (description "CONNECT 1")
      (libsource (lib "hanguyen") (part "TP"))
    )
    (comp (ref "TP3")
      (value "1")
      (footprint "TP - 2")
      (description "CONNECT 1")
      (libsource (lib "") (part "TP_1"))
    )
    (comp (ref "U1")
      (value "TI TPS563203DRLR")
      (footprint "SOT50P160X60-6N:SOT50P160X60-6N")
      (description "ICS OCV BCK TPS563201 3A SOT23-6 SMD")
      (libsource (lib "2502-GMQLITE-MAIN") (part "ICSOCV0021 BCK TPS563201 3A SOT23-6 SMD"))
    )
    (comp (ref "U2")
      (value "TI TPS563203DRLR")
      (footprint "SOT50P160X60-6N:SOT50P160X60-6N")
      (description "ICS OCV BCK TPS563201 3A SOT23-6 SMD")
      (libsource (lib "2502-GMQLITE-MAIN") (part "ICSOCV0021 BCK TPS563201 3A SOT23-6 SMD"))
    )
    (comp (ref "U3")
      (value "AP2112K-3.3TRG1")
      (footprint "AP2112K-3P3TRG1:SOT_RG1_DIO")
      (description "AP2112 Series 0.6 A 3.3 V Fixed Output SMT LDO Linear Regulator - SOT23-5")
      (fields (field (name "MF") "Diodes Inc."))
      (libsource (lib "hanguyen") (part "AP2112K-3.3TRG1"))
    )
    (comp (ref "U4")
      (value "TCA9534APWR")
      (footprint "SOP65P640X120-16N")
      (description "8-bit 1.65- to 5.5-V I2C/SMBus I/O expander with interrupt, & config registers")
      (fields (field (name "MF") "Texas Instruments"))
      (libsource (lib "TCA9534APWR") (part "TCA9534APWR"))
    )
    (comp (ref "U5")
      (value "MPRLS0025PA00001A")
      (footprint "SnapEDApcb:XDCR_MPRLS0025PA00001A")
      (description "Pressure Sensor 25PSI _172.37kPa_ Absolute Male - 0.1 _2.5mm_ Tube 24 b 12-SMD Module")
      (fields (field (name "DIGI-KEY_PART_NUMBER") "480-7098-1-ND") (field (name "MF") "Honeywell Sensing"))
      (libsource (lib "SnapEDAsch") (part "MPRLS0025PA00001A"))
    )
    (comp (ref "U6")
      (value "PCA9632DP2,118")
      (footprint "TSSOP10_3P1X3P1_NXP")
      (description "No Description Available")
      (fields (field (name "COPYRIGHT") "Copyright (C) 2026 Ultra Librarian. All rights reserved."))
      (libsource (lib "PCA9632DP2,118") (part "PCA9632DP2,118"))
    )
    (comp (ref "U7")
      (value "PUMP")
      (footprint "Pump")
      (description "Connector Header 2 Position 6.35mm Solder Straight Thru-Hole 2 Terminal 1 Port MLX-Series")
      (fields (field (name "MANUFACTURER") "Molex") (field (name "MANUFACTURER PART NUMBER") "10-84-4022"))
      (libsource (lib "LIB_PRESSURE") (part "A5F083"))
    )
    (comp (ref "U8")
      (value "PUMP")
      (footprint "Pump")
      (description "Connector Header 2 Position 6.35mm Solder Straight Thru-Hole 2 Terminal 1 Port MLX-Series")
      (fields (field (name "MANUFACTURER") "Molex") (field (name "MANUFACTURER PART NUMBER") "10-84-4022"))
      (libsource (lib "LIB_PRESSURE") (part "A5F083"))
    )
    (comp (ref "U9")
      (value "VALVE")
      (footprint "VALVE")
      (description "Connector Header 2 Position 6.35mm Solder Straight Thru-Hole 2 Terminal 1 Port MLX-Series")
      (fields (field (name "MANUFACTURER") "Molex") (field (name "MANUFACTURER PART NUMBER") "10-84-4022"))
      (libsource (lib "LIB_PRESSURE") (part "A5F083"))
    )
    (comp (ref "U10")
      (value "VALVE2")
      (footprint "VALVE")
      (description "Connector Header 2 Position 6.35mm Solder Straight Thru-Hole 2 Terminal 1 Port MLX-Series")
      (fields (field (name "MANUFACTURER") "Molex") (field (name "MANUFACTURER PART NUMBER") "10-84-4022"))
      (libsource (lib "LIB_PRESSURE") (part "A5F083"))
    )
  )
  (nets
    (net (code "1") (name "+12") (class "Default")
      (node (ref "D1") (pin "1") (pinfunction "A_1") (pintype "passive"))
      (node (ref "JDC1") (pin "1") (pinfunction "T_1") (pintype "passive"))
    )
    (net (code "2") (name "/LED0") (class "Default")
      (node (ref "LED6") (pin "2") (pinfunction "2_2") (pintype "passive"))
      (node (ref "U6") (pin "1") (pinfunction "LED0_1") (pintype "bidirectional"))
    )
    (net (code "3") (name "/LED1") (class "Default")
      (node (ref "LED5") (pin "2") (pinfunction "2_2") (pintype "passive"))
      (node (ref "U6") (pin "2") (pinfunction "LED1_2") (pintype "bidirectional"))
    )
    (net (code "4") (name "/LED2") (class "Default")
      (node (ref "R23") (pin "2") (pinfunction "2_2") (pintype "passive"))
      (node (ref "U6") (pin "3") (pinfunction "LED2_3") (pintype "bidirectional"))
    )
    (net (code "5") (name "/LED3") (class "Default")
      (node (ref "R25") (pin "1") (pinfunction "1_1") (pintype "passive"))
      (node (ref "U6") (pin "4") (pinfunction "LED3_4") (pintype "bidirectional"))
    )
    (net (code "6") (name "/PUMP1") (class "Default")
      (node (ref "R30") (pin "1") (pinfunction "1_1") (pintype "passive"))
      (node (ref "U4") (pin "4") (pinfunction "P0_4") (pintype "bidirectional"))
    )
    (net (code "7") (name "/PUMP2") (class "Default")
      (node (ref "R33") (pin "1") (pinfunction "1_1") (pintype "passive"))
      (node (ref "U4") (pin "7") (pinfunction "P3_7") (pintype "bidirectional"))
    )
    (net (code "8") (name "/RES") (class "Default")
      (node (ref "R11") (pin "2") (pinfunction "2_2") (pintype "passive"))
      (node (ref "TP2") (pin "1") (pinfunction "TP_1") (pintype "passive"))
      (node (ref "U5") (pin "9") (pinfunction "RES_9") (pintype "input"))
    )
    (net (code "9") (name "/SCL") (class "Default")
      (node (ref "J1") (pin "4") (pinfunction "4_4") (pintype "passive"))
      (node (ref "J2") (pin "4") (pinfunction "4_4") (pintype "passive"))
      (node (ref "J3") (pin "4") (pinfunction "4_4") (pintype "passive"))
      (node (ref "J4") (pin "4") (pinfunction "4_4") (pintype "passive"))
      (node (ref "J5") (pin "4") (pinfunction "4_4") (pintype "passive"))
      (node (ref "R10") (pin "2") (pinfunction "2_2") (pintype "passive"))
      (node (ref "R22") (pin "2") (pinfunction "2_2") (pintype "passive"))
      (node (ref "U4") (pin "14") (pinfunction "SCL_14") (pintype "input"))
      (node (ref "U6") (pin "8") (pinfunction "SCL_8") (pintype "passive"))
    )
    (net (code "10") (name "/SDA") (class "Default")
      (node (ref "J1") (pin "3") (pinfunction "3_3") (pintype "passive"))
      (node (ref "J2") (pin "3") (pinfunction "3_3") (pintype "passive"))
      (node (ref "J3") (pin "3") (pinfunction "3_3") (pintype "passive"))
      (node (ref "J4") (pin "3") (pinfunction "3_3") (pintype "passive"))
      (node (ref "J5") (pin "3") (pinfunction "3_3") (pintype "passive"))
      (node (ref "R21") (pin "2") (pinfunction "2_2") (pintype "passive"))
      (node (ref "R9") (pin "2") (pinfunction "2_2") (pintype "passive"))
      (node (ref "U4") (pin "15") (pinfunction "SDA_15") (pintype "bidirectional"))
      (node (ref "U6") (pin "9") (pinfunction "SDA_9") (pintype "passive"))
    )
    (net (code "11") (name "/SW3") (class "Default")
      (node (ref "C23") (pin "2") (pinfunction "2_2") (pintype "passive"))
      (node (ref "R12") (pin "1") (pinfunction "1_1") (pintype "passive"))
      (node (ref "SW1") (pin "1") (pinfunction "1_1") (pintype "passive"))
      (node (ref "SW1") (pin "2") (pinfunction "2_2") (pintype "passive"))
    )
    (net (code "12") (name "/SW6") (class "Default")
      (node (ref "C24") (pin "2") (pinfunction "2_2") (pintype "passive"))
      (node (ref "R13") (pin "1") (pinfunction "1_1") (pintype "passive"))
      (node (ref "SW2") (pin "1") (pinfunction "1_1") (pintype "passive"))
      (node (ref "SW2") (pin "2") (pinfunction "2_2") (pintype "passive"))
    )
    (net (code "13") (name "/VALVE1") (class "Default")
      (node (ref "C29") (pin "2") (pinfunction "2_2") (pintype "passive"))
      (node (ref "R29") (pin "1") (pinfunction "1_1") (pintype "passive"))
      (node (ref "R37") (pin "1") (pinfunction "1_1") (pintype "passive"))
      (node (ref "SW4") (pin "1") (pinfunction "1_1") (pintype "passive"))
      (node (ref "SW4") (pin "2") (pinfunction "2_2") (pintype "passive"))
      (node (ref "U4") (pin "6") (pinfunction "P2_6") (pintype "bidirectional"))
    )
    (net (code "14") (name "/VALVE2") (class "Default")
      (node (ref "C28") (pin "2") (pinfunction "2_2") (pintype "passive"))
      (node (ref "R28") (pin "1") (pinfunction "1_1") (pintype "passive"))
      (node (ref "R38") (pin "1") (pinfunction "1_1") (pintype "passive"))
      (node (ref "SW3") (pin "1") (pinfunction "1_1") (pintype "passive"))
      (node (ref "SW3") (pin "2") (pinfunction "2_2") (pintype "passive"))
      (node (ref "U4") (pin "5") (pinfunction "P1_5") (pintype "bidirectional"))
    )
    (net (code "15") (name "3V3") (class "Default")
      (node (ref "C16") (pin "2") (pinfunction "2_2") (pintype "passive"))
      (node (ref "C17") (pin "2") (pinfunction "2_2") (pintype "passive"))
      (node (ref "FB1") (pin "1") (pinfunction "1_1") (pintype "passive"))
      (node (ref "U3") (pin "5") (pinfunction "VOUT_5") (pintype "power_in"))
    )
    (net (code "16") (name "4V5") (class "Default")
      (node (ref "C27") (pin "1") (pinfunction "1_1") (pintype "passive"))
      (node (ref "C30") (pin "1") (pinfunction "1_1") (pintype "passive"))
      (node (ref "C4") (pin "2") (pinfunction "2_2") (pintype "passive"))
      (node (ref "C5") (pin "2") (pinfunction "2_2") (pintype "passive"))
      (node (ref "C6") (pin "2") (pinfunction "2_2") (pintype "passive"))
      (node (ref "C7") (pin "2") (pinfunction "2_2") (pintype "passive"))
      (node (ref "D4") (pin "1") (pinfunction "A_1") (pintype "passive"))
      (node (ref "D5") (pin "2") (pinfunction "K_2") (pintype "passive"))
      (node (ref "D6") (pin "1") (pinfunction "A_1") (pintype "passive"))
      (node (ref "D7") (pin "2") (pinfunction "K_2") (pintype "passive"))
      (node (ref "F1") (pin "1") (pinfunction "1_1") (pintype "passive"))
      (node (ref "L1") (pin "2") (pinfunction "2_2") (pintype "passive"))
      (node (ref "R2") (pin "2") (pinfunction "2_2") (pintype "passive"))
      (node (ref "U7") (pin "1") (pinfunction "+_1") (pintype "passive"))
      (node (ref "U8") (pin "1") (pinfunction "+_1") (pintype "passive"))
    )
    (net (code "17") (name "4V5A") (class "Default")
      (node (ref "C15") (pin "2") (pinfunction "2_2") (pintype "passive"))
      (node (ref "D2") (pin "1") (pinfunction "A_1") (pintype "passive"))
      (node (ref "F1") (pin "2") (pinfunction "2_2") (pintype "passive"))
      (node (ref "U3") (pin "1") (pinfunction "VIN_1") (pintype "power_in"))
      (node (ref "U3") (pin "3") (pinfunction "EN_3") (pintype "input"))
    )
    (net (code "18") (name "6V") (class "Default")
      (node (ref "C11") (pin "2") (pinfunction "2_2") (pintype "passive"))
      (node (ref "C12") (pin "2") (pinfunction "2_2") (pintype "passive"))
      (node (ref "C13") (pin "2") (pinfunction "2_2") (pintype "passive"))
      (node (ref "C14") (pin "2") (pinfunction "2_2") (pintype "passive"))
      (node (ref "C31") (pin "1") (pinfunction "1_1") (pintype "passive"))
      (node (ref "C32") (pin "1") (pinfunction "1_1") (pintype "passive"))
      (node (ref "D10") (pin "2") (pinfunction "K_2") (pintype "passive"))
      (node (ref "D11") (pin "2") (pinfunction "K_2") (pintype "passive"))
      (node (ref "D8") (pin "1") (pinfunction "A_1") (pintype "passive"))
      (node (ref "D9") (pin "1") (pinfunction "A_1") (pintype "passive"))
      (node (ref "L2") (pin "2") (pinfunction "2_2") (pintype "passive"))
      (node (ref "R5") (pin "2") (pinfunction "2_2") (pintype "passive"))
      (node (ref "U10") (pin "1") (pinfunction "+_1") (pintype "passive"))
      (node (ref "U9") (pin "1") (pinfunction "+_1") (pintype "passive"))
    )
    (net (code "19") (name "D3V3") (class "Default")
      (node (ref "C18") (pin "2") (pinfunction "2_2") (pintype "passive"))
      (node (ref "C19") (pin "1") (pinfunction "1_1") (pintype "passive"))
      (node (ref "C20") (pin "2") (pinfunction "2_2") (pintype "passive"))
      (node (ref "C22") (pin "2") (pinfunction "2_2") (pintype "passive"))
      (node (ref "C25") (pin "2") (pinfunction "2_2") (pintype "passive"))
      (node (ref "C26") (pin "2") (pinfunction "2_2") (pintype "passive"))
      (node (ref "FB1") (pin "2") (pinfunction "2_2") (pintype "passive"))
      (node (ref "J1") (pin "2") (pinfunction "2_2") (pintype "passive"))
      (node (ref "J2") (pin "2") (pinfunction "2_2") (pintype "passive"))
      (node (ref "J3") (pin "1") (pinfunction "1_1") (pintype "passive"))
      (node (ref "J4") (pin "2") (pinfunction "2_2") (pintype "passive"))
      (node (ref "J5") (pin "2") (pinfunction "2_2") (pintype "passive"))
      (node (ref "JP1") (pin "2") (pinfunction "2_2") (pintype "passive"))
      (node (ref "R10") (pin "1") (pinfunction "1_1") (pintype "passive"))
      (node (ref "R11") (pin "1") (pinfunction "1_1") (pintype "passive"))
      (node (ref "R12") (pin "2") (pinfunction "2_2") (pintype "passive"))
      (node (ref "R13") (pin "2") (pinfunction "2_2") (pintype "passive"))
      (node (ref "R14") (pin "1") (pinfunction "1_1") (pintype "passive"))
      (node (ref "R15") (pin "1") (pinfunction "1_1") (pintype "passive"))
      (node (ref "R16") (pin "1") (pinfunction "1_1") (pintype "passive"))
      (node (ref "R17") (pin "1") (pinfunction "1_1") (pintype "passive"))
      (node (ref "R18") (pin "1") (pinfunction "1_1") (pintype "passive"))
      (node (ref "R19") (pin "1") (pinfunction "1_1") (pintype "passive"))
      (node (ref "R20") (pin "1") (pinfunction "1_1") (pintype "passive"))
      (node (ref "R21") (pin "1") (pinfunction "1_1") (pintype "passive"))
      (node (ref "R22") (pin "1") (pinfunction "1_1") (pintype "passive"))
      (node (ref "R28") (pin "2") (pinfunction "2_2") (pintype "passive"))
      (node (ref "R29") (pin "2") (pinfunction "2_2") (pintype "passive"))
      (node (ref "R8") (pin "1") (pinfunction "1_1") (pintype "passive"))
      (node (ref "R9") (pin "1") (pinfunction "1_1") (pintype "passive"))
      (node (ref "U4") (pin "1") (pinfunction "A0_1") (pintype "input"))
      (node (ref "U4") (pin "16") (pinfunction "VCC_16") (pintype "power_in"))
      (node (ref "U4") (pin "2") (pinfunction "A1_2") (pintype "input"))
      (node (ref "U4") (pin "3") (pinfunction "A2_3") (pintype "input"))
      (node (ref "U6") (pin "10") (pinfunction "VDD_10") (pintype "power_in"))
      (node (ref "U6") (pin "5") (pinfunction "A0_5") (pintype "bidirectional"))
    )
    (net (code "20") (name "GND") (class "Default")
      (node (ref "C10") (pin "1") (pinfunction "1_1") (pintype "passive"))
      (node (ref "C12") (pin "1") (pinfunction "1_1") (pintype "passive"))
      (node (ref "C13") (pin "1") (pinfunction "1_1") (pintype "passive"))
      (node (ref "C14") (pin "1") (pinfunction "1_1") (pintype "passive"))
      (node (ref "C15") (pin "1") (pinfunction "1_1") (pintype "passive"))
      (node (ref "C16") (pin "1") (pinfunction "1_1") (pintype "passive"))
      (node (ref "C17") (pin "1") (pinfunction "1_1") (pintype "passive"))
      (node (ref "C18") (pin "1") (pinfunction "1_1") (pintype "passive"))
      (node (ref "C19") (pin "2") (pinfunction "2_2") (pintype "passive"))
      (node (ref "C2") (pin "1") (pinfunction "1_1") (pintype "passive"))
      (node (ref "C20") (pin "1") (pinfunction "1_1") (pintype "passive"))
      (node (ref "C22") (pin "1") (pinfunction "1_1") (pintype "passive"))
      (node (ref "C23") (pin "1") (pinfunction "1_1") (pintype "passive"))
      (node (ref "C24") (pin "1") (pinfunction "1_1") (pintype "passive"))
      (node (ref "C25") (pin "1") (pinfunction "1_1") (pintype "passive"))
      (node (ref "C26") (pin "1") (pinfunction "1_1") (pintype "passive"))
      (node (ref "C27") (pin "2") (pinfunction "2_2") (pintype "passive"))
      (node (ref "C28") (pin "1") (pinfunction "1_1") (pintype "passive"))
      (node (ref "C29") (pin "1") (pinfunction "1_1") (pintype "passive"))
      (node (ref "C3") (pin "1") (pinfunction "1_1") (pintype "passive"))
      (node (ref "C30") (pin "2") (pinfunction "2_2") (pintype "passive"))
      (node (ref "C31") (pin "2") (pinfunction "2_2") (pintype "passive"))
      (node (ref "C32") (pin "2") (pinfunction "2_2") (pintype "passive"))
      (node (ref "C5") (pin "1") (pinfunction "1_1") (pintype "passive"))
      (node (ref "C6") (pin "1") (pinfunction "1_1") (pintype "passive"))
      (node (ref "C7") (pin "1") (pinfunction "1_1") (pintype "passive"))
      (node (ref "C9") (pin "1") (pinfunction "1_1") (pintype "passive"))
      (node (ref "D3") (pin "2") (pinfunction "K_2") (pintype "passive"))
      (node (ref "J1") (pin "1") (pinfunction "1_1") (pintype "passive"))
      (node (ref "J2") (pin "1") (pinfunction "1_1") (pintype "passive"))
      (node (ref "J3") (pin "2") (pinfunction "2_2") (pintype "passive"))
      (node (ref "J4") (pin "1") (pinfunction "1_1") (pintype "passive"))
      (node (ref "J5") (pin "1") (pinfunction "1_1") (pintype "passive"))
      (node (ref "JDC1") (pin "2") (pinfunction "TN_2") (pintype "passive"))
      (node (ref "JDC1") (pin "3") (pinfunction "S_3") (pintype "power_in"))
      (node (ref "Q3") (pin "2") (pinfunction "S_2") (pintype "passive"))
      (node (ref "Q4") (pin "2") (pinfunction "S_2") (pintype "passive"))
      (node (ref "Q5") (pin "2") (pinfunction "S_2") (pintype "passive"))
      (node (ref "Q6") (pin "2") (pinfunction "S_2") (pintype "passive"))
      (node (ref "R24") (pin "2") (pinfunction "2_2") (pintype "passive"))
      (node (ref "R26") (pin "2") (pinfunction "2_2") (pintype "passive"))
      (node (ref "R3") (pin "1") (pinfunction "1_1") (pintype "passive"))
      (node (ref "R31") (pin "1") (pinfunction "1_1") (pintype "passive"))
      (node (ref "R34") (pin "1") (pinfunction "1_1") (pintype "passive"))
      (node (ref "R39") (pin "1") (pinfunction "1_1") (pintype "passive"))
      (node (ref "R40") (pin "1") (pinfunction "1_1") (pintype "passive"))
      (node (ref "R6") (pin "1") (pinfunction "1_1") (pintype "passive"))
      (node (ref "R7") (pin "2") (pinfunction "2_2") (pintype "passive"))
      (node (ref "SW1") (pin "3") (pinfunction "3_3") (pintype "passive"))
      (node (ref "SW1") (pin "4") (pinfunction "4_4") (pintype "passive"))
      (node (ref "SW2") (pin "3") (pinfunction "3_3") (pintype "passive"))
      (node (ref "SW2") (pin "4") (pinfunction "4_4") (pintype "passive"))
      (node (ref "SW3") (pin "3") (pinfunction "3_3") (pintype "passive"))
      (node (ref "SW3") (pin "4") (pinfunction "4_4") (pintype "passive"))
      (node (ref "SW4") (pin "3") (pinfunction "3_3") (pintype "passive"))
      (node (ref "SW4") (pin "4") (pinfunction "4_4") (pintype "passive"))
      (node (ref "U1") (pin "3") (pinfunction "GND_3") (pintype "power_in"))
      (node (ref "U2") (pin "3") (pinfunction "GND_3") (pintype "power_in"))
      (node (ref "U3") (pin "2") (pinfunction "GND_2") (pintype "power_in"))
      (node (ref "U4") (pin "8") (pinfunction "GND_8") (pintype "power_in"))
      (node (ref "U5") (pin "10") (pinfunction "VSS_10") (pintype "power_in"))
      (node (ref "U6") (pin "6") (pinfunction "VSS_6") (pintype "power_in"))
      (node (ref "U6") (pin "7") (pinfunction "A1_7") (pintype "bidirectional"))
    )
    (net (code "21") (name "Net-(D2-K)") (class "Default")
      (node (ref "D2") (pin "2") (pinfunction "K_2") (pintype "passive"))
      (node (ref "R7") (pin "1") (pinfunction "1_1") (pintype "passive"))
    )
    (net (code "22") (name "Net-(D3-A)") (class "Default")
      (node (ref "D3") (pin "1") (pinfunction "A_1") (pintype "passive"))
      (node (ref "R14") (pin "2") (pinfunction "2_2") (pintype "passive"))
    )
    (net (code "23") (name "Net-(D4-K)") (class "Default")
      (node (ref "D4") (pin "2") (pinfunction "K_2") (pintype "passive"))
      (node (ref "R27") (pin "2") (pinfunction "2_2") (pintype "passive"))
    )
    (net (code "24") (name "Net-(D5-A)") (class "Default")
      (node (ref "D5") (pin "1") (pinfunction "A_1") (pintype "passive"))
      (node (ref "Q3") (pin "3") (pinfunction "D_3") (pintype "passive"))
      (node (ref "R27") (pin "1") (pinfunction "1_1") (pintype "passive"))
      (node (ref "U7") (pin "2") (pinfunction "-_2") (pintype "passive"))
    )
    (net (code "25") (name "Net-(D6-K)") (class "Default")
      (node (ref "D6") (pin "2") (pinfunction "K_2") (pintype "passive"))
      (node (ref "R32") (pin "2") (pinfunction "2_2") (pintype "passive"))
    )
    (net (code "26") (name "Net-(D7-A)") (class "Default")
      (node (ref "D7") (pin "1") (pinfunction "A_1") (pintype "passive"))
      (node (ref "Q4") (pin "3") (pinfunction "D_3") (pintype "passive"))
      (node (ref "R32") (pin "1") (pinfunction "1_1") (pintype "passive"))
      (node (ref "U8") (pin "2") (pinfunction "-_2") (pintype "passive"))
    )
    (net (code "27") (name "Net-(D8-K)") (class "Default")
      (node (ref "D8") (pin "2") (pinfunction "K_2") (pintype "passive"))
      (node (ref "R35") (pin "2") (pinfunction "2_2") (pintype "passive"))
    )
    (net (code "28") (name "Net-(D9-K)") (class "Default")
      (node (ref "D9") (pin "2") (pinfunction "K_2") (pintype "passive"))
      (node (ref "R36") (pin "2") (pinfunction "2_2") (pintype "passive"))
    )
    (net (code "29") (name "Net-(D10-A)") (class "Default")
      (node (ref "D10") (pin "1") (pinfunction "A_1") (pintype "passive"))
      (node (ref "Q6") (pin "3") (pinfunction "D_3") (pintype "passive"))
      (node (ref "R35") (pin "1") (pinfunction "1_1") (pintype "passive"))
      (node (ref "U9") (pin "2") (pinfunction "-_2") (pintype "passive"))
    )
    (net (code "30") (name "Net-(D11-A)") (class "Default")
      (node (ref "D11") (pin "1") (pinfunction "A_1") (pintype "passive"))
      (node (ref "Q5") (pin "3") (pinfunction "D_3") (pintype "passive"))
      (node (ref "R36") (pin "1") (pinfunction "1_1") (pintype "passive"))
      (node (ref "U10") (pin "2") (pinfunction "-_2") (pintype "passive"))
    )
    (net (code "31") (name "Net-(LED1-Pad1)") (class "Default")
      (node (ref "LED1") (pin "1") (pinfunction "1_1") (pintype "passive"))
      (node (ref "R20") (pin "2") (pinfunction "2_2") (pintype "passive"))
    )
    (net (code "32") (name "Net-(LED1-Pad2)") (class "Default")
      (node (ref "LED1") (pin "2") (pinfunction "2_2") (pintype "passive"))
      (node (ref "LED7") (pin "1") (pinfunction "1_1") (pintype "passive"))
    )
    (net (code "33") (name "Net-(LED2-Pad1)") (class "Default")
      (node (ref "LED2") (pin "1") (pinfunction "1_1") (pintype "passive"))
      (node (ref "R15") (pin "2") (pinfunction "2_2") (pintype "passive"))
    )
    (net (code "34") (name "Net-(LED3-Pad1)") (class "Default")
      (node (ref "LED3") (pin "1") (pinfunction "1_1") (pintype "passive"))
      (node (ref "R16") (pin "2") (pinfunction "2_2") (pintype "passive"))
    )
    (net (code "35") (name "Net-(LED4-Pad1)") (class "Default")
      (node (ref "LED4") (pin "1") (pinfunction "1_1") (pintype "passive"))
      (node (ref "R17") (pin "2") (pinfunction "2_2") (pintype "passive"))
    )
    (net (code "36") (name "Net-(LED5-Pad1)") (class "Default")
      (node (ref "LED5") (pin "1") (pinfunction "1_1") (pintype "passive"))
      (node (ref "R18") (pin "2") (pinfunction "2_2") (pintype "passive"))
    )
    (net (code "37") (name "Net-(LED6-Pad1)") (class "Default")
      (node (ref "LED6") (pin "1") (pinfunction "1_1") (pintype "passive"))
      (node (ref "R19") (pin "2") (pinfunction "2_2") (pintype "passive"))
    )
    (net (code "38") (name "Net-(LED7-Pad2)") (class "Default")
      (node (ref "LED7") (pin "2") (pinfunction "2_2") (pintype "passive"))
      (node (ref "LED8") (pin "1") (pinfunction "1_1") (pintype "passive"))
    )
    (net (code "39") (name "Net-(Q1-D)") (class "Default")
      (node (ref "Q1") (pin "3") (pinfunction "D_3") (pintype "passive"))
      (node (ref "R24") (pin "1") (pinfunction "1_1") (pintype "passive"))
    )
    (net (code "40") (name "Net-(Q1-G)") (class "Default")
      (node (ref "Q1") (pin "1") (pinfunction "G_1") (pintype "passive"))
      (node (ref "R23") (pin "1") (pinfunction "1_1") (pintype "passive"))
    )
    (net (code "41") (name "Net-(Q1-S)") (class "Default")
      (node (ref "LED2") (pin "2") (pinfunction "2_2") (pintype "passive"))
      (node (ref "LED3") (pin "2") (pinfunction "2_2") (pintype "passive"))
      (node (ref "LED4") (pin "2") (pinfunction "2_2") (pintype "passive"))
      (node (ref "Q1") (pin "2") (pinfunction "S_2") (pintype "passive"))
    )
    (net (code "42") (name "Net-(Q2-D)") (class "Default")
      (node (ref "Q2") (pin "3") (pinfunction "D_3") (pintype "passive"))
      (node (ref "R26") (pin "1") (pinfunction "1_1") (pintype "passive"))
    )
    (net (code "43") (name "Net-(Q2-G)") (class "Default")
      (node (ref "Q2") (pin "1") (pinfunction "G_1") (pintype "passive"))
      (node (ref "R25") (pin "2") (pinfunction "2_2") (pintype "passive"))
    )
    (net (code "44") (name "Net-(Q2-S)") (class "Default")
      (node (ref "LED8") (pin "2") (pinfunction "2_2") (pintype "passive"))
      (node (ref "Q2") (pin "2") (pinfunction "S_2") (pintype "passive"))
    )
    (net (code "45") (name "Net-(Q3-G)") (class "Default")
      (node (ref "Q3") (pin "1") (pinfunction "G_1") (pintype "passive"))
      (node (ref "R30") (pin "2") (pinfunction "2_2") (pintype "passive"))
      (node (ref "R31") (pin "2") (pinfunction "2_2") (pintype "passive"))
    )
    (net (code "46") (name "Net-(Q4-G)") (class "Default")
      (node (ref "Q4") (pin "1") (pinfunction "G_1") (pintype "passive"))
      (node (ref "R33") (pin "2") (pinfunction "2_2") (pintype "passive"))
      (node (ref "R34") (pin "2") (pinfunction "2_2") (pintype "passive"))
    )
    (net (code "47") (name "Net-(Q5-G)") (class "Default")
      (node (ref "Q5") (pin "1") (pinfunction "G_1") (pintype "passive"))
      (node (ref "R37") (pin "2") (pinfunction "2_2") (pintype "passive"))
      (node (ref "R39") (pin "2") (pinfunction "2_2") (pintype "passive"))
    )
    (net (code "48") (name "Net-(Q6-G)") (class "Default")
      (node (ref "Q6") (pin "1") (pinfunction "G_1") (pintype "passive"))
      (node (ref "R38") (pin "2") (pinfunction "2_2") (pintype "passive"))
      (node (ref "R40") (pin "2") (pinfunction "2_2") (pintype "passive"))
    )
    (net (code "49") (name "Net-(TP1-TP)") (class "Default")
      (node (ref "R8") (pin "2") (pinfunction "2_2") (pintype "passive"))
      (node (ref "TP1") (pin "1") (pinfunction "TP_1") (pintype "passive"))
      (node (ref "U4") (pin "13") (pinfunction "/INT_13") (pintype "output"))
    )
    (net (code "50") (name "Net-(TP3-TP)") (class "Default")
      (node (ref "TP3") (pin "1") (pinfunction "TP_1") (pintype "passive"))
      (node (ref "U5") (pin "8") (pinfunction "EOC_8") (pintype "output"))
    )
    (net (code "51") (name "Net-(U1-BST)") (class "Default")
      (node (ref "C1") (pin "2") (pinfunction "2_2") (pintype "passive"))
      (node (ref "U1") (pin "4") (pinfunction "BST_4") (pintype "passive"))
    )
    (net (code "52") (name "Net-(U1-EN)") (class "Default")
      (node (ref "R1") (pin "1") (pinfunction "1_1") (pintype "passive"))
      (node (ref "U1") (pin "5") (pinfunction "EN_5") (pintype "passive"))
    )
    (net (code "53") (name "Net-(U1-FB)") (class "Default")
      (node (ref "C4") (pin "1") (pinfunction "1_1") (pintype "passive"))
      (node (ref "R2") (pin "1") (pinfunction "1_1") (pintype "passive"))
      (node (ref "R3") (pin "2") (pinfunction "2_2") (pintype "passive"))
      (node (ref "U1") (pin "6") (pinfunction "FB_6") (pintype "passive"))
    )
    (net (code "54") (name "Net-(U1-SW)") (class "Default")
      (node (ref "C1") (pin "1") (pinfunction "1_1") (pintype "passive"))
      (node (ref "L1") (pin "1") (pinfunction "1_1") (pintype "passive"))
      (node (ref "U1") (pin "2") (pinfunction "SW_2") (pintype "passive"))
    )
    (net (code "55") (name "Net-(U2-BST)") (class "Default")
      (node (ref "C8") (pin "2") (pinfunction "2_2") (pintype "passive"))
      (node (ref "U2") (pin "4") (pinfunction "BST_4") (pintype "passive"))
    )
    (net (code "56") (name "Net-(U2-EN)") (class "Default")
      (node (ref "R4") (pin "1") (pinfunction "1_1") (pintype "passive"))
      (node (ref "U2") (pin "5") (pinfunction "EN_5") (pintype "passive"))
    )
    (net (code "57") (name "Net-(U2-FB)") (class "Default")
      (node (ref "C11") (pin "1") (pinfunction "1_1") (pintype "passive"))
      (node (ref "R5") (pin "1") (pinfunction "1_1") (pintype "passive"))
      (node (ref "R6") (pin "2") (pinfunction "2_2") (pintype "passive"))
      (node (ref "U2") (pin "6") (pinfunction "FB_6") (pintype "passive"))
    )
    (net (code "58") (name "Net-(U2-SW)") (class "Default")
      (node (ref "C8") (pin "1") (pinfunction "1_1") (pintype "passive"))
      (node (ref "L2") (pin "1") (pinfunction "1_1") (pintype "passive"))
      (node (ref "U2") (pin "2") (pinfunction "SW_2") (pintype "passive"))
    )
    (net (code "59") (name "Net-(U5-VDD)") (class "Default")
      (node (ref "JP1") (pin "1") (pinfunction "1_1") (pintype "passive"))
      (node (ref "U5") (pin "12") (pinfunction "VDD_12") (pintype "power_in"))
    )
    (net (code "60") (name "Net-(U5-VO+)") (class "Default")
      (node (ref "C21") (pin "2") (pinfunction "2_2") (pintype "passive"))
      (node (ref "U5") (pin "4") (pinfunction "VO+_4") (pintype "output"))
    )
    (net (code "61") (name "Net-(U5-VO-)") (class "Default")
      (node (ref "C21") (pin "1") (pinfunction "1_1") (pintype "passive"))
      (node (ref "U5") (pin "6") (pinfunction "VO-_6") (pintype "output"))
    )
    (net (code "62") (name "VIN") (class "Default")
      (node (ref "C10") (pin "2") (pinfunction "2_2") (pintype "passive"))
      (node (ref "C2") (pin "2") (pinfunction "2_2") (pintype "passive"))
      (node (ref "C3") (pin "2") (pinfunction "2_2") (pintype "passive"))
      (node (ref "C9") (pin "2") (pinfunction "2_2") (pintype "passive"))
      (node (ref "D1") (pin "2") (pinfunction "K_2") (pintype "passive"))
      (node (ref "R1") (pin "2") (pinfunction "2_2") (pintype "passive"))
      (node (ref "R4") (pin "2") (pinfunction "2_2") (pintype "passive"))
      (node (ref "U1") (pin "1") (pinfunction "IN_1") (pintype "power_in"))
      (node (ref "U2") (pin "1") (pinfunction "IN_1") (pintype "power_in"))
    )
    (net (code "63") (name "unconnected-(U4-P4-Pad9)") (class "Default")
      (node (ref "U4") (pin "9") (pinfunction "P4_9") (pintype "bidirectional+no_connect"))
    )
    (net (code "64") (name "unconnected-(U4-P5-Pad10)") (class "Default")
      (node (ref "U4") (pin "10") (pinfunction "P5_10") (pintype "bidirectional+no_connect"))
    )
    (net (code "65") (name "unconnected-(U4-P6-Pad11)") (class "Default")
      (node (ref "U4") (pin "11") (pinfunction "P6_11") (pintype "bidirectional+no_connect"))
    )
    (net (code "66") (name "unconnected-(U4-P7-Pad12)") (class "Default")
      (node (ref "U4") (pin "12") (pinfunction "P7_12") (pintype "bidirectional+no_connect"))
    )
    (net (code "67") (name "unconnected-(U5-MISO-Pad7)") (class "Default")
      (node (ref "U5") (pin "7") (pinfunction "MISO_7") (pintype "output+no_connect"))
    )
    (net (code "68") (name "unconnected-(U5-MOSI{slash}SDA-Pad2)") (class "Default")
      (node (ref "U5") (pin "2") (pinfunction "MOSI/SDA_2") (pintype "bidirectional+no_connect"))
    )
    (net (code "69") (name "unconnected-(U5-SCLK{slash}SCL-Pad3)") (class "Default")
      (node (ref "U5") (pin "3") (pinfunction "SCLK/SCL_3") (pintype "input+no_connect"))
    )
    (net (code "70") (name "unconnected-(U5-SS-Pad1)") (class "Default")
      (node (ref "U5") (pin "1") (pinfunction "SS_1") (pintype "input+no_connect"))
    )
  )
)
